# BSB-to-PoELAN.net
KiCad netlist of a schematic drawn in EAGLE
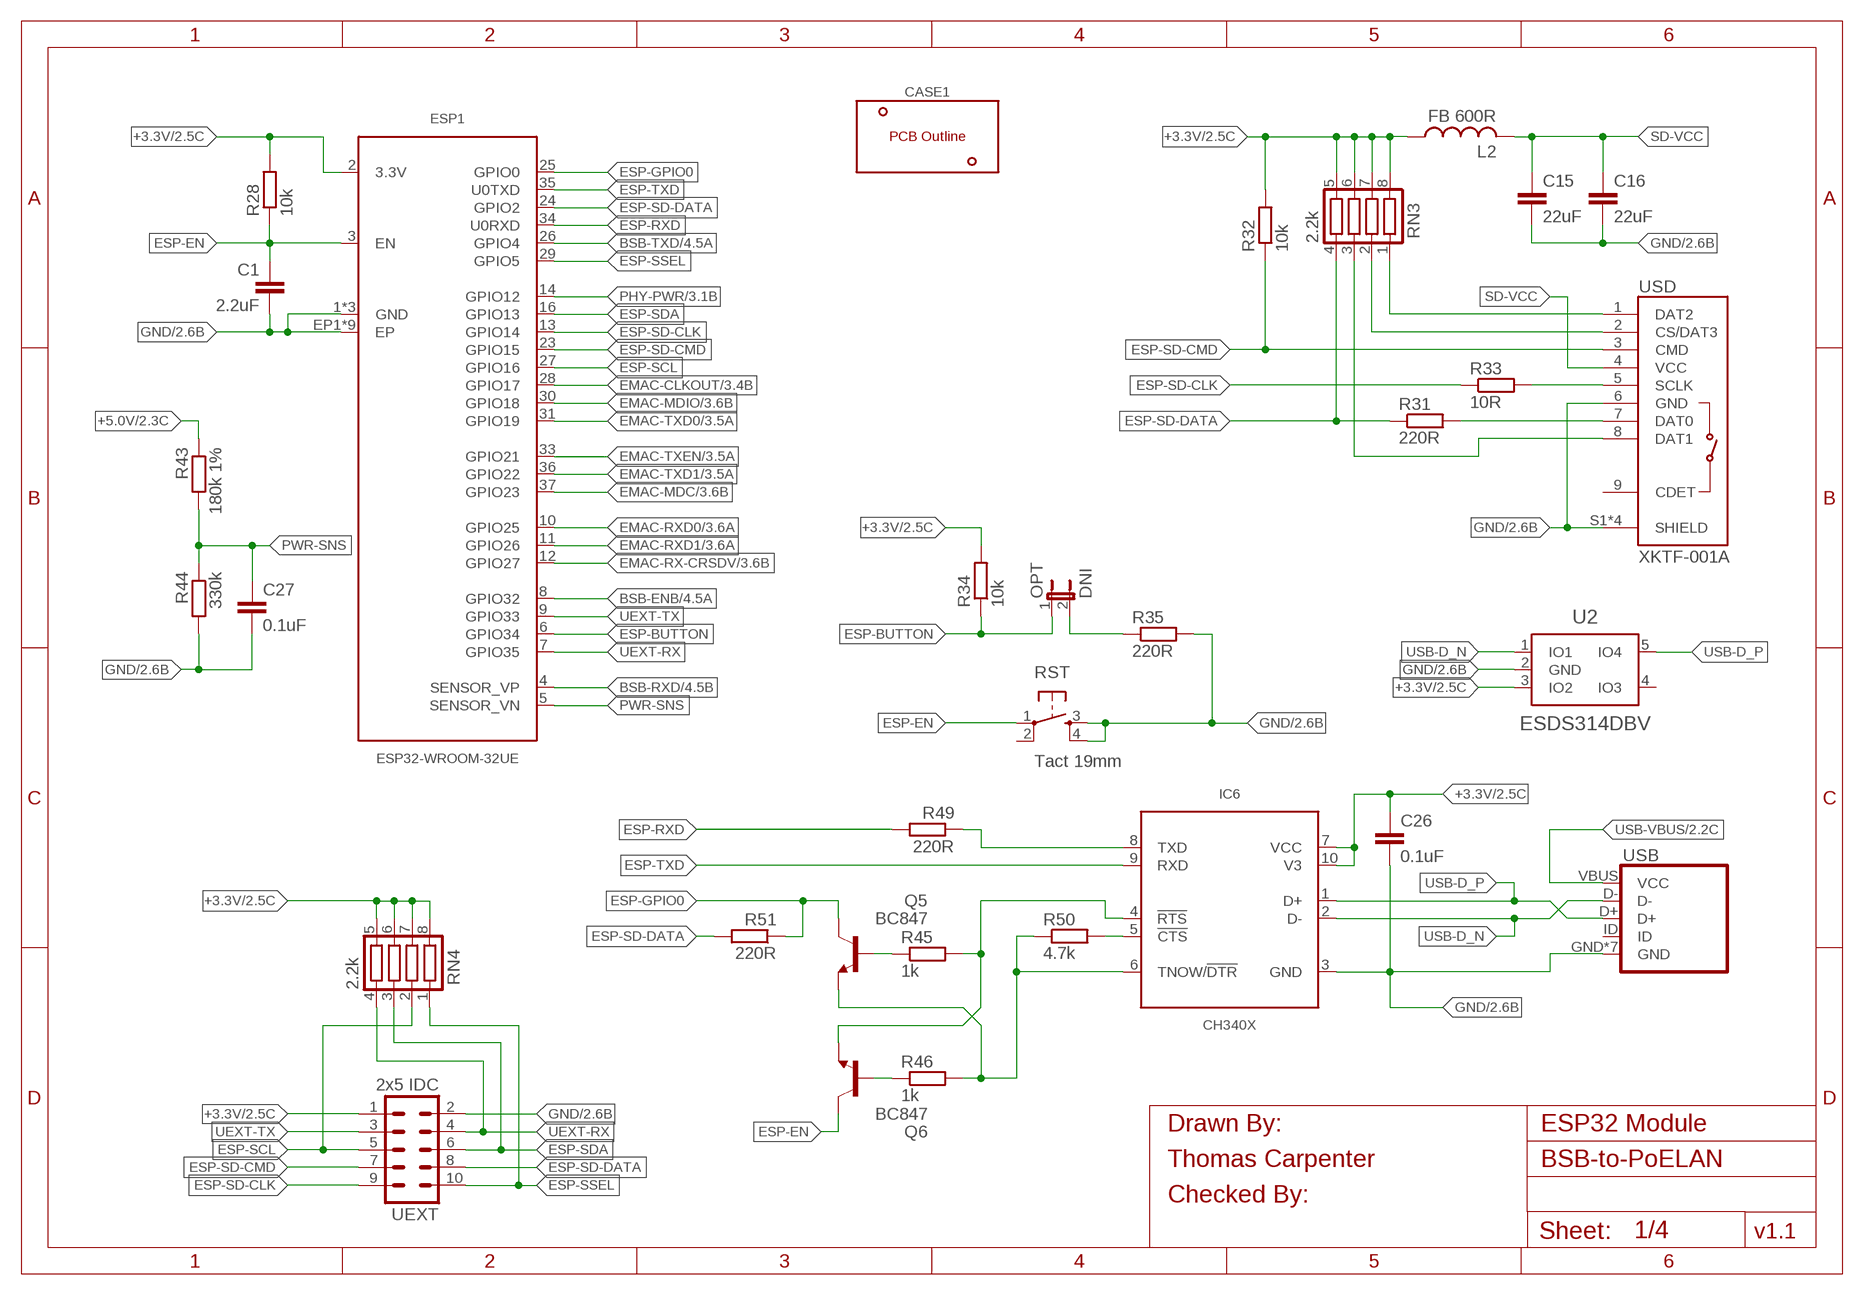
[diagram p0: schematic, sheet 1]
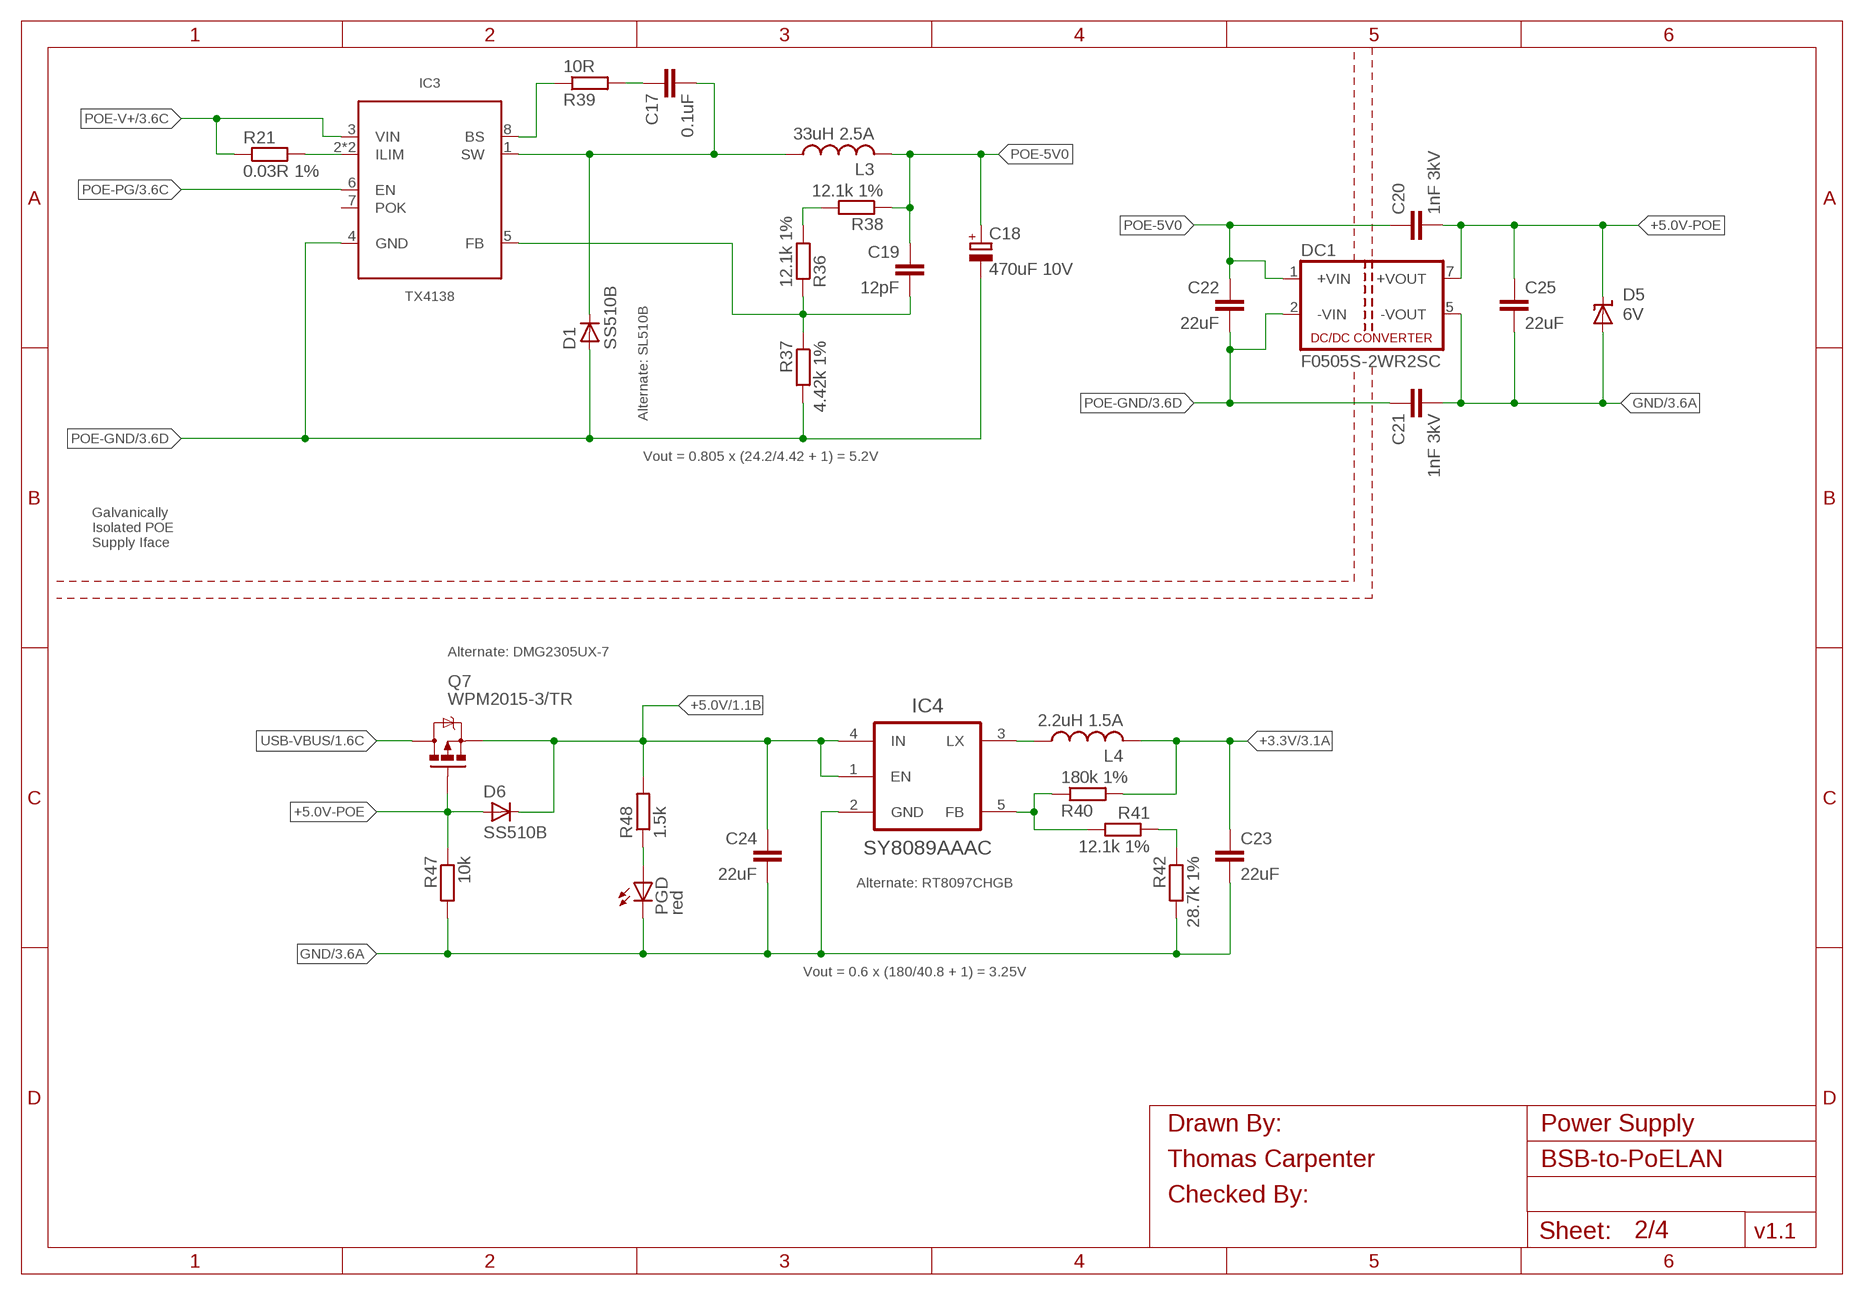
[diagram p1: schematic, sheet 2]
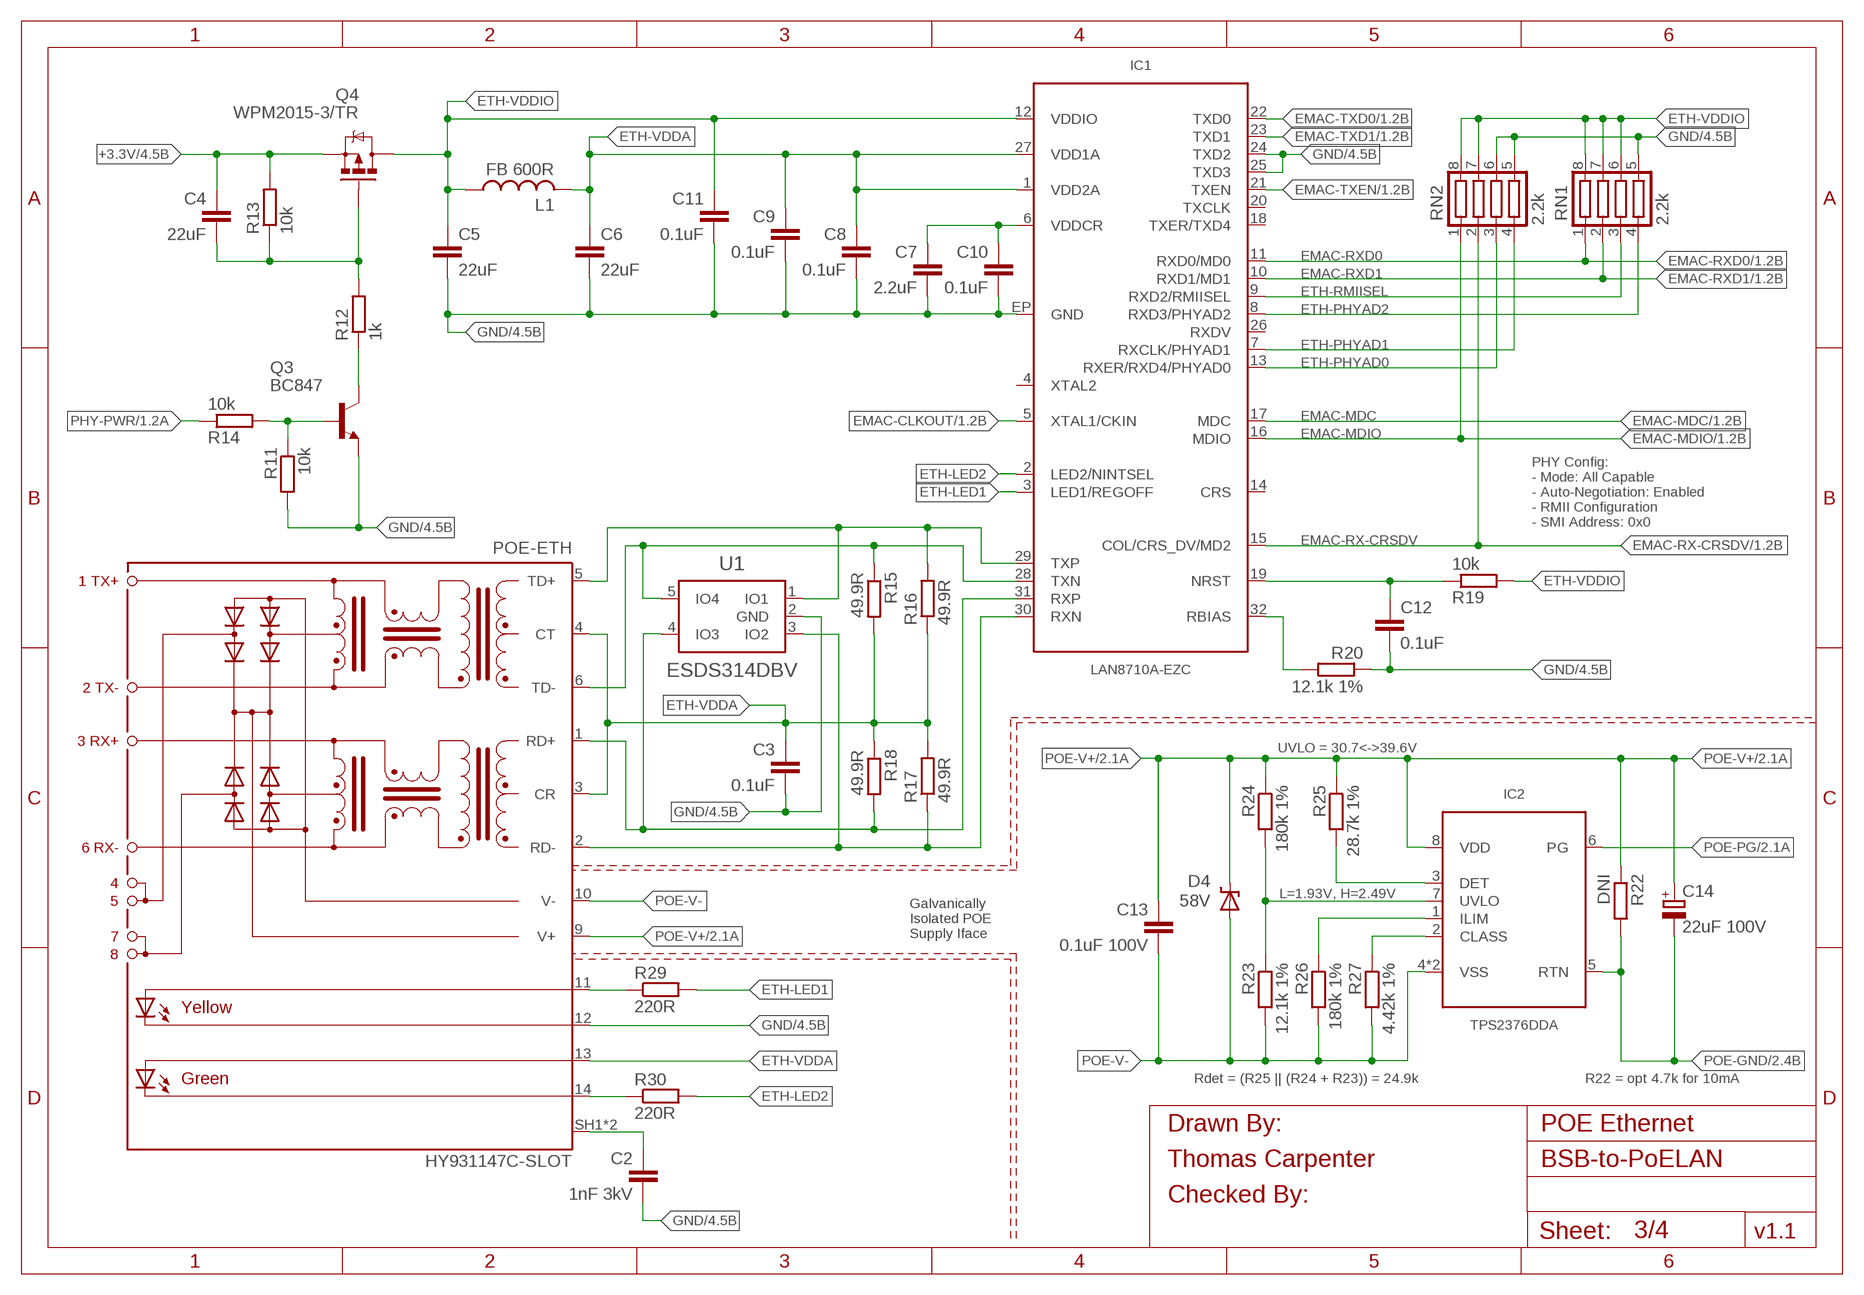
[diagram p2: schematic, sheet 3]
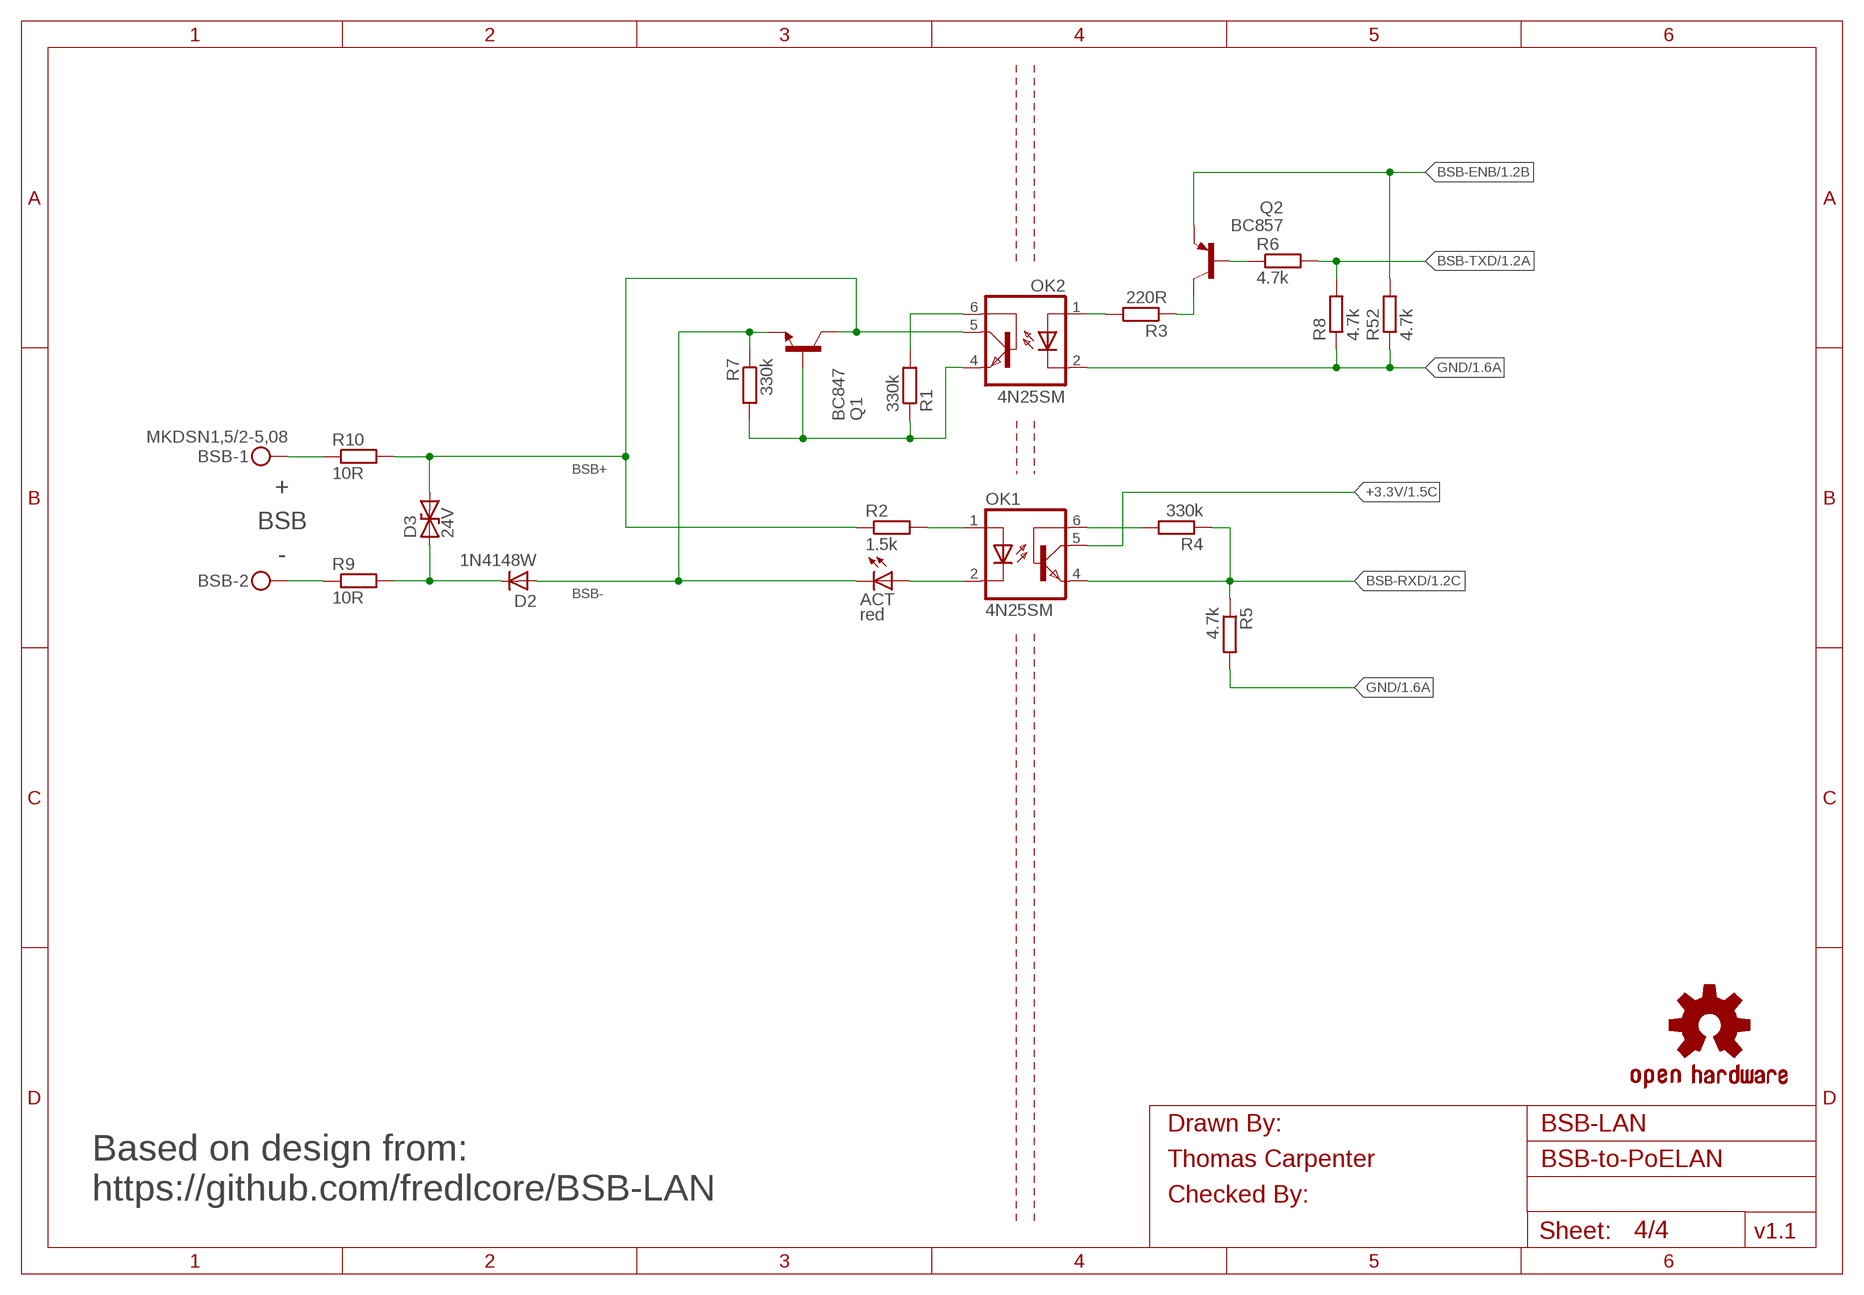
[diagram p3: schematic, sheet 4]

(export (version "E")
  (design (tool "Eeschema 10.0.6"))
  (components
    (comp (ref "C17")
      (value "0.1uF")
      (footprint "eagle-import:C0603L")
      (fields (field (name "LCSC_PART") "C113803"))
      (libsource (lib "eagle-import") (part "C-EUC0603L"))
    )
    (comp (ref "C18")
      (value "470uF 10V")
      (footprint "eagle-import:SMC_D")
      (fields (field (name "LCSC_PART") "C4944894"))
      (libsource (lib "eagle-import") (part "CPOL-EUSMCD"))
    )
    (comp (ref "C19")
      (value "12pF")
      (footprint "eagle-import:C0402")
      (fields (field (name "LCSC_PART") "C1547"))
      (libsource (lib "eagle-import") (part "C-EUC0402"))
    )
    (comp (ref "C20")
      (value "1nF 3kV")
      (footprint "eagle-import:C1808")
      (fields (field (name "LCSC_PART") "C577300"))
      (libsource (lib "eagle-import") (part "C-EUC1808"))
    )
    (comp (ref "C21")
      (value "1nF 3kV")
      (footprint "eagle-import:C1808")
      (fields (field (name "LCSC_PART") "C577300"))
      (libsource (lib "eagle-import") (part "C-EUC1808"))
    )
    (comp (ref "C22")
      (value "22uF")
      (footprint "eagle-import:C0805")
      (fields (field (name "LCSC_PART") "C45783"))
      (libsource (lib "eagle-import") (part "C-EUC0805"))
    )
    (comp (ref "C23")
      (value "22uF")
      (footprint "eagle-import:C0805")
      (fields (field (name "LCSC_PART") "C45783"))
      (libsource (lib "eagle-import") (part "C-EUC0805"))
    )
    (comp (ref "C24")
      (value "22uF")
      (footprint "eagle-import:C0805")
      (fields (field (name "LCSC_PART") "C45783"))
      (libsource (lib "eagle-import") (part "C-EUC0805"))
    )
    (comp (ref "C25")
      (value "22uF")
      (footprint "eagle-import:C0805")
      (fields (field (name "LCSC_PART") "C45783"))
      (libsource (lib "eagle-import") (part "C-EUC0805"))
    )
    (comp (ref "D1")
      (value "SS510B")
      (footprint "eagle-import:SMB")
      (fields (field (name "LCSC_PART") "C65011"))
      (libsource (lib "eagle-import") (part "DIODE-SMB"))
    )
    (comp (ref "D5")
      (value "6V")
      (footprint "eagle-import:SMA")
      (fields (field (name "LCSC_PART") "C223993"))
      (libsource (lib "eagle-import") (part "TVS-UNISMA"))
    )
    (comp (ref "D6")
      (value "SS510B")
      (footprint "eagle-import:SMB")
      (fields (field (name "LCSC_PART") "C65011"))
      (libsource (lib "eagle-import") (part "DIODE-SMB"))
    )
    (comp (ref "DC1")
      (value "F0505S-2WR2SC")
      (footprint "eagle-import:SIP7-N")
      (fields (field (name "LCSC_PART") "C909777"))
      (libsource (lib "eagle-import") (part "FS-2WR2SC0505"))
    )
    (comp (ref "IC3")
      (value "TX4138")
      (footprint "eagle-import:SOIC8-EP")
      (fields (field (name "LCSC_PART") "C329267"))
      (libsource (lib "eagle-import") (part "TX4138"))
    )
    (comp (ref "IC4")
      (value "SY8089AAAC")
      (footprint "eagle-import:DBV0005A-SOT23")
      (fields (field (name "LCSC_PART") "C78988"))
      (libsource (lib "eagle-import") (part "SY8089?CAAA"))
    )
    (comp (ref "L3")
      (value "33uH 2.5A")
      (footprint "eagle-import:L6560P")
      (fields (field (name "LCSC_PART") "C2839927"))
      (libsource (lib "eagle-import") (part "L-USL6560P"))
    )
    (comp (ref "L4")
      (value "2.2uH 1.5A")
      (footprint "eagle-import:L4040P")
      (fields (field (name "LCSC_PART") "C135262"))
      (libsource (lib "eagle-import") (part "L-USL4040P"))
    )
    (comp (ref "PGD")
      (value "red")
      (footprint "eagle-import:CHIP-LED0603")
      (fields (field (name "LCSC_PART") "C2286"))
      (libsource (lib "eagle-import") (part "LEDCHIPLED_0603"))
    )
    (comp (ref "Q7")
      (value "WPM2015-3/TR")
      (footprint "eagle-import:SOT23")
      (fields (field (name "LCSC_PART") "C7472861"))
      (libsource (lib "eagle-import") (part "WPM2015-3/TR"))
    )
    (comp (ref "R21")
      (value "0.03R 1%")
      (footprint "eagle-import:R1206")
      (fields (field (name "LCSC_PART") "C163046"))
      (libsource (lib "eagle-import") (part "R-EU_R1206"))
    )
    (comp (ref "R36")
      (value "12.1k 1%")
      (footprint "eagle-import:R0402")
      (fields (field (name "LCSC_PART") "C25852"))
      (libsource (lib "eagle-import") (part "R-EU_R0402"))
    )
    (comp (ref "R37")
      (value "4.42k 1%")
      (footprint "eagle-import:R0402")
      (fields (field (name "LCSC_PART") "C52269"))
      (libsource (lib "eagle-import") (part "R-EU_R0402"))
    )
    (comp (ref "R38")
      (value "12.1k 1%")
      (footprint "eagle-import:R0402")
      (fields (field (name "LCSC_PART") "C25852"))
      (libsource (lib "eagle-import") (part "R-EU_R0402"))
    )
    (comp (ref "R39")
      (value "10R")
      (footprint "eagle-import:R0603L")
      (fields (field (name "LCSC_PART") "C22859"))
      (libsource (lib "eagle-import") (part "R-EU_R0603L"))
    )
    (comp (ref "R40")
      (value "180k 1%")
      (footprint "eagle-import:R0402")
      (fields (field (name "LCSC_PART") "C25760"))
      (libsource (lib "eagle-import") (part "R-EU_R0402"))
    )
    (comp (ref "R41")
      (value "12.1k 1%")
      (footprint "eagle-import:R0402")
      (fields (field (name "LCSC_PART") "C25852"))
      (libsource (lib "eagle-import") (part "R-EU_R0402"))
    )
    (comp (ref "R42")
      (value "28.7k 1%")
      (footprint "eagle-import:R0402")
      (fields (field (name "LCSC_PART") "C26972"))
      (libsource (lib "eagle-import") (part "R-EU_R0402"))
    )
    (comp (ref "R47")
      (value "10k")
      (footprint "eagle-import:R0402")
      (fields (field (name "LCSC_PART") "C25744"))
      (libsource (lib "eagle-import") (part "R-EU_R0402"))
    )
    (comp (ref "R48")
      (value "1.5k")
      (footprint "eagle-import:R0603")
      (fields (field (name "LCSC_PART") "C22843"))
      (libsource (lib "eagle-import") (part "R-EU_R0603"))
    )
    (comp (ref "C2")
      (value "1nF 3kV")
      (footprint "eagle-import:C1808")
      (fields (field (name "LCSC_PART") "C577300"))
      (libsource (lib "eagle-import") (part "C-EUC1808"))
    )
    (comp (ref "C3")
      (value "0.1uF")
      (footprint "eagle-import:C0402")
      (fields (field (name "LCSC_PART") "C1525"))
      (libsource (lib "eagle-import") (part "C-EUC0402"))
    )
    (comp (ref "C4")
      (value "22uF")
      (footprint "eagle-import:C0805L")
      (fields (field (name "LCSC_PART") "C45783"))
      (libsource (lib "eagle-import") (part "C-EUC0805L"))
    )
    (comp (ref "C5")
      (value "22uF")
      (footprint "eagle-import:C0805L")
      (fields (field (name "LCSC_PART") "C45783"))
      (libsource (lib "eagle-import") (part "C-EUC0805L"))
    )
    (comp (ref "C6")
      (value "22uF")
      (footprint "eagle-import:C0805L")
      (fields (field (name "LCSC_PART") "C45783"))
      (libsource (lib "eagle-import") (part "C-EUC0805L"))
    )
    (comp (ref "C7")
      (value "2.2uF")
      (footprint "eagle-import:C0603")
      (fields (field (name "LCSC_PART") "C23630"))
      (libsource (lib "eagle-import") (part "C-EUC0603"))
    )
    (comp (ref "C8")
      (value "0.1uF")
      (footprint "eagle-import:C0402")
      (fields (field (name "LCSC_PART") "C1525"))
      (libsource (lib "eagle-import") (part "C-EUC0402"))
    )
    (comp (ref "C9")
      (value "0.1uF")
      (footprint "eagle-import:C0402")
      (fields (field (name "LCSC_PART") "C1525"))
      (libsource (lib "eagle-import") (part "C-EUC0402"))
    )
    (comp (ref "C10")
      (value "0.1uF")
      (footprint "eagle-import:C0402")
      (fields (field (name "LCSC_PART") "C1525"))
      (libsource (lib "eagle-import") (part "C-EUC0402"))
    )
    (comp (ref "C11")
      (value "0.1uF")
      (footprint "eagle-import:C0402")
      (fields (field (name "LCSC_PART") "C1525"))
      (libsource (lib "eagle-import") (part "C-EUC0402"))
    )
    (comp (ref "C12")
      (value "0.1uF")
      (footprint "eagle-import:C0402")
      (fields (field (name "LCSC_PART") "C1525"))
      (libsource (lib "eagle-import") (part "C-EUC0402"))
    )
    (comp (ref "C13")
      (value "0.1uF 100V")
      (footprint "eagle-import:C0603")
      (fields (field (name "LCSC_PART") "C113803"))
      (libsource (lib "eagle-import") (part "C-EUC0603"))
    )
    (comp (ref "C14")
      (value "22uF 100V")
      (footprint "eagle-import:PANASONIC_D")
      (fields (field (name "LCSC_PART") "C487431"))
      (libsource (lib "eagle-import") (part "CPOL-EUD"))
    )
    (comp (ref "D4")
      (value "58V")
      (footprint "eagle-import:SMA")
      (fields (field (name "LCSC_PART") "C151246"))
      (libsource (lib "eagle-import") (part "TVS-UNISMA"))
    )
    (comp (ref "IC1")
      (value "LAN8710A-EZC")
      (footprint "eagle-import:QFN-5X5-32")
      (fields (field (name "LCSC_PART") "C46185"))
      (libsource (lib "eagle-import") (part "LAN8710A-EZC"))
    )
    (comp (ref "IC2")
      (value "TPS2376DDA")
      (footprint "eagle-import:SOIC8-EP")
      (fields (field (name "LCSC_PART") "C544899"))
      (libsource (lib "eagle-import") (part "TPS237DDA6"))
    )
    (comp (ref "L1")
      (value "FB 600R")
      (footprint "eagle-import:L2010")
      (fields (field (name "LCSC_PART") "C1017"))
      (libsource (lib "eagle-import") (part "L-USL0805"))
    )
    (comp (ref "POE-ETH")
      (value "HY931147C-SLOT")
      (footprint "eagle-import:HY931147C-SLOT")
      (fields (field (name "LCSC_PART") "C91754"))
      (libsource (lib "eagle-import") (part "HY931147C-SLOT"))
    )
    (comp (ref "Q3")
      (value "BC847")
      (footprint "eagle-import:SOT23")
      (fields (field (name "LCSC_PART") "C130417"))
      (libsource (lib "eagle-import") (part "BC847"))
    )
    (comp (ref "Q4")
      (value "WPM2015-3/TR")
      (footprint "eagle-import:SOT23")
      (fields (field (name "LCSC_PART") "C7472861"))
      (libsource (lib "eagle-import") (part "WPM2015-3/TR"))
    )
    (comp (ref "R11")
      (value "10k")
      (footprint "eagle-import:R0402")
      (fields (field (name "LCSC_PART") "C25744"))
      (libsource (lib "eagle-import") (part "R-EU_R0402"))
    )
    (comp (ref "R12")
      (value "1k")
      (footprint "eagle-import:R0402")
      (fields (field (name "LCSC_PART") "C11702"))
      (libsource (lib "eagle-import") (part "R-EU_R0402"))
    )
    (comp (ref "R13")
      (value "10k")
      (footprint "eagle-import:R0402")
      (fields (field (name "LCSC_PART") "C25744"))
      (libsource (lib "eagle-import") (part "R-EU_R0402"))
    )
    (comp (ref "R14")
      (value "10k")
      (footprint "eagle-import:R0402")
      (fields (field (name "LCSC_PART") "C25744"))
      (libsource (lib "eagle-import") (part "R-EU_R0402"))
    )
    (comp (ref "R15")
      (value "49.9R")
      (footprint "eagle-import:R0402L")
      (fields (field (name "LCSC_PART") "C25120"))
      (libsource (lib "eagle-import") (part "R-EU_R0402L"))
    )
    (comp (ref "R16")
      (value "49.9R")
      (footprint "eagle-import:R0402L")
      (fields (field (name "LCSC_PART") "C25120"))
      (libsource (lib "eagle-import") (part "R-EU_R0402L"))
    )
    (comp (ref "R17")
      (value "49.9R")
      (footprint "eagle-import:R0402L")
      (fields (field (name "LCSC_PART") "C25120"))
      (libsource (lib "eagle-import") (part "R-EU_R0402L"))
    )
    (comp (ref "R18")
      (value "49.9R")
      (footprint "eagle-import:R0402L")
      (fields (field (name "LCSC_PART") "C25120"))
      (libsource (lib "eagle-import") (part "R-EU_R0402L"))
    )
    (comp (ref "R19")
      (value "10k")
      (footprint "eagle-import:R0402")
      (fields (field (name "LCSC_PART") "C25744"))
      (libsource (lib "eagle-import") (part "R-EU_R0402"))
    )
    (comp (ref "R20")
      (value "12.1k 1%")
      (footprint "eagle-import:R0402")
      (fields (field (name "LCSC_PART") "C25852"))
      (libsource (lib "eagle-import") (part "R-EU_R0402"))
    )
    (comp (ref "R22")
      (value "DNI")
      (footprint "eagle-import:R1206")
      (libsource (lib "eagle-import") (part "R-EU_R1206"))
    )
    (comp (ref "R23")
      (value "12.1k 1%")
      (footprint "eagle-import:R0402")
      (fields (field (name "LCSC_PART") "C25852"))
      (libsource (lib "eagle-import") (part "R-EU_R0402"))
    )
    (comp (ref "R24")
      (value "180k 1%")
      (footprint "eagle-import:R0402")
      (fields (field (name "LCSC_PART") "C25760"))
      (libsource (lib "eagle-import") (part "R-EU_R0402"))
    )
    (comp (ref "R25")
      (value "28.7k 1%")
      (footprint "eagle-import:R0402")
      (fields (field (name "LCSC_PART") "C26972"))
      (libsource (lib "eagle-import") (part "R-EU_R0402"))
    )
    (comp (ref "R26")
      (value "180k 1%")
      (footprint "eagle-import:R0402")
      (fields (field (name "LCSC_PART") "C25760"))
      (libsource (lib "eagle-import") (part "R-EU_R0402"))
    )
    (comp (ref "R27")
      (value "4.42k 1%")
      (footprint "eagle-import:R0402")
      (fields (field (name "LCSC_PART") "C52269"))
      (libsource (lib "eagle-import") (part "R-EU_R0402"))
    )
    (comp (ref "R29")
      (value "220R")
      (footprint "eagle-import:R0402")
      (fields (field (name "LCSC_PART") "C25091"))
      (libsource (lib "eagle-import") (part "R-EU_R0402"))
    )
    (comp (ref "R30")
      (value "220R")
      (footprint "eagle-import:R0402")
      (fields (field (name "LCSC_PART") "C25091"))
      (libsource (lib "eagle-import") (part "R-EU_R0402"))
    )
    (comp (ref "RN1")
      (value "2.2k")
      (footprint "eagle-import:CTS742C083")
      (fields (field (name "LCSC_PART") "C414564"))
      (libsource (lib "eagle-import") (part "R-NET-04-R1206"))
    )
    (comp (ref "RN2")
      (value "2.2k")
      (footprint "eagle-import:CTS742C083")
      (fields (field (name "LCSC_PART") "C414564"))
      (libsource (lib "eagle-import") (part "R-NET-04-R1206"))
    )
    (comp (ref "U1")
      (value "ESDS314DBV")
      (footprint "eagle-import:DBV0005A-SOT23")
      (fields (field (name "LCSC_PART") "C1847859"))
      (libsource (lib "eagle-import") (part "ESDS314DBV"))
    )
    (comp (ref "C1")
      (value "2.2uF")
      (footprint "eagle-import:C0603")
      (fields (field (name "LCSC_PART") "C23630"))
      (libsource (lib "eagle-import") (part "C-EUC0603"))
    )
    (comp (ref "C15")
      (value "22uF")
      (footprint "eagle-import:C0805L")
      (fields (field (name "LCSC_PART") "C45783"))
      (libsource (lib "eagle-import") (part "C-EUC0805L"))
    )
    (comp (ref "C16")
      (value "22uF")
      (footprint "eagle-import:C0805L")
      (fields (field (name "LCSC_PART") "C45783"))
      (libsource (lib "eagle-import") (part "C-EUC0805L"))
    )
    (comp (ref "C26")
      (value "0.1uF")
      (footprint "eagle-import:C0402")
      (fields (field (name "LCSC_PART") "C1525"))
      (libsource (lib "eagle-import") (part "C-EUC0402"))
    )
    (comp (ref "C27")
      (value "0.1uF")
      (footprint "eagle-import:C0402")
      (fields (field (name "LCSC_PART") "C1525"))
      (libsource (lib "eagle-import") (part "C-EUC0402"))
    )
    (comp (ref "CASE1")
      (value "DNI")
      (footprint "eagle-import:CNMB_3-")
      (libsource (lib "eagle-import") (part "CNMB/3"))
    )
    (comp (ref "ESP1")
      (value "ESP32-WROOM-32UE")
      (footprint "eagle-import:ESP32-WROOM-32UE")
      (fields (field (name "LCSC_PART") "C701344"))
      (libsource (lib "eagle-import") (part "ESP32-WROOM-32UE"))
    )
    (comp (ref "IC6")
      (value "CH340X")
      (footprint "eagle-import:MSOP10")
      (fields (field (name "LCSC_PART") "C3035748"))
      (libsource (lib "eagle-import") (part "CH340X"))
    )
    (comp (ref "L2")
      (value "FB 600R")
      (footprint "eagle-import:L2010")
      (fields (field (name "LCSC_PART") "C1017"))
      (libsource (lib "eagle-import") (part "L-USL0805"))
    )
    (comp (ref "OPT")
      (value "DNI")
      (footprint "eagle-import:1X02")
      (libsource (lib "eagle-import") (part "JUMPER-2-PTH"))
    )
    (comp (ref "Q5")
      (value "BC847")
      (footprint "eagle-import:SOT23")
      (fields (field (name "LCSC_PART") "C130417") (field (name "LCSC_PART_1") "C130417"))
      (libsource (lib "eagle-import") (part "BC847"))
    )
    (comp (ref "Q6")
      (value "BC847")
      (footprint "eagle-import:SOT23")
      (fields (field (name "LCSC_PART") "C130417"))
      (libsource (lib "eagle-import") (part "BC847"))
    )
    (comp (ref "R28")
      (value "10k")
      (footprint "eagle-import:R0402")
      (fields (field (name "LCSC_PART") "C25744"))
      (libsource (lib "eagle-import") (part "R-EU_R0402"))
    )
    (comp (ref "R31")
      (value "220R")
      (footprint "eagle-import:R0402")
      (fields (field (name "LCSC_PART") "C25091"))
      (libsource (lib "eagle-import") (part "R-EU_R0402"))
    )
    (comp (ref "R32")
      (value "10k")
      (footprint "eagle-import:R0402")
      (fields (field (name "LCSC_PART") "C25744"))
      (libsource (lib "eagle-import") (part "R-EU_R0402"))
    )
    (comp (ref "R33")
      (value "10R")
      (footprint "eagle-import:R0603L")
      (fields (field (name "LCSC_PART") "C22859"))
      (libsource (lib "eagle-import") (part "R-EU_R0603L"))
    )
    (comp (ref "R34")
      (value "10k")
      (footprint "eagle-import:R0402")
      (fields (field (name "LCSC_PART") "C25744"))
      (libsource (lib "eagle-import") (part "R-EU_R0402"))
    )
    (comp (ref "R35")
      (value "220R")
      (footprint "eagle-import:R0402")
      (fields (field (name "LCSC_PART") "C25091"))
      (libsource (lib "eagle-import") (part "R-EU_R0402"))
    )
    (comp (ref "R43")
      (value "180k 1%")
      (footprint "eagle-import:R0402")
      (fields (field (name "LCSC_PART") "C25760"))
      (libsource (lib "eagle-import") (part "R-EU_R0402"))
    )
    (comp (ref "R44")
      (value "330k")
      (footprint "eagle-import:R0603L")
      (fields (field (name "LCSC_PART") "C23137"))
      (libsource (lib "eagle-import") (part "R-EU_R0603L"))
    )
    (comp (ref "R45")
      (value "1k")
      (footprint "eagle-import:R0402")
      (fields (field (name "LCSC_PART") "C11702"))
      (libsource (lib "eagle-import") (part "R-EU_R0402"))
    )
    (comp (ref "R46")
      (value "1k")
      (footprint "eagle-import:R0402")
      (fields (field (name "LCSC_PART") "C11702"))
      (libsource (lib "eagle-import") (part "R-EU_R0402"))
    )
    (comp (ref "R49")
      (value "220R")
      (footprint "eagle-import:R0402")
      (fields (field (name "LCSC_PART") "C25091"))
      (libsource (lib "eagle-import") (part "R-EU_R0402"))
    )
    (comp (ref "R50")
      (value "4.7k")
      (footprint "eagle-import:R0402")
      (fields (field (name "LCSC_PART") "C25900"))
      (libsource (lib "eagle-import") (part "R-EU_R0402"))
    )
    (comp (ref "R51")
      (value "220R")
      (footprint "eagle-import:R0402")
      (fields (field (name "LCSC_PART") "C25091"))
      (libsource (lib "eagle-import") (part "R-EU_R0402"))
    )
    (comp (ref "RN3")
      (value "2.2k")
      (footprint "eagle-import:CTS742C083")
      (fields (field (name "LCSC_PART") "C414564"))
      (libsource (lib "eagle-import") (part "R-NET-04-R1206"))
    )
    (comp (ref "RN4")
      (value "2.2k")
      (footprint "eagle-import:CTS742C083")
      (fields (field (name "LCSC_PART") "C414564"))
      (libsource (lib "eagle-import") (part "R-NET-04-R1206"))
    )
    (comp (ref "RST")
      (value "Tact 19mm")
      (footprint "eagle-import:TACTILE_SWITCH")
      (fields (field (name "LCSC_PART") "C13828") (field (name "LCSC_PART_1") "C2837529"))
      (libsource (lib "eagle-import") (part "SWITCH-MOMENTARY"))
    )
    (comp (ref "U2")
      (value "ESDS314DBV")
      (footprint "eagle-import:DBV0005A-SOT23")
      (fields (field (name "LCSC_PART") "C1847859"))
      (libsource (lib "eagle-import") (part "ESDS314DBV"))
    )
    (comp (ref "UEXT")
      (value "2x5 IDC")
      (footprint "eagle-import:ML10")
      (fields (field (name "LCSC_PART") "C5665"))
      (libsource (lib "eagle-import") (part "ML10"))
    )
    (comp (ref "USB")
      (value "ZX62-B-5PA(33)")
      (footprint "eagle-import:USB-MICROB")
      (fields (field (name "LCSC_PART") "C132561"))
      (libsource (lib "eagle-import") (part "USB_MICROB_PLUG"))
    )
    (comp (ref "USD")
      (value "XKTF-001A")
      (footprint "eagle-import:MICRO-SD")
      (fields (field (name "LCSC_PART") "C381079"))
      (libsource (lib "eagle-import") (part "MICROSD"))
    )
    (comp (ref "ACT")
      (value "red")
      (footprint "eagle-import:CHIP-LED0603")
      (fields (field (name "LCSC_PART") "C2286"))
      (libsource (lib "eagle-import") (part "LEDCHIPLED_0603"))
    )
    (comp (ref "BSB")
      (value "MKDSN1,5/2-5,08")
      (footprint "eagle-import:MKDSN1_5-2-5_08")
      (fields (field (name "LCSC_PART") "C5183989"))
      (libsource (lib "eagle-import") (part "MKDSN1,5/2-5,08"))
    )
    (comp (ref "D2")
      (value "1N4148W")
      (footprint "eagle-import:SOD123")
      (fields (field (name "LCSC_PART") "C81598"))
      (libsource (lib "eagle-import") (part "DIODE-SOD123"))
    )
    (comp (ref "D3")
      (value "24V")
      (footprint "eagle-import:SMBG")
      (fields (field (name "LCSC_PART") "C83268"))
      (libsource (lib "eagle-import") (part "TVS-BIDIRSMB"))
    )
    (comp (ref "OK1")
      (value "4N25SM")
      (footprint "eagle-import:DIL6-SMD")
      (fields (field (name "LCSC_PART") "C258246") (field (name "LCSC_PART_1") "C258246"))
      (libsource (lib "eagle-import") (part "4N?MS25"))
    )
    (comp (ref "OK2")
      (value "4N25SM")
      (footprint "eagle-import:DIL6-SMD")
      (fields (field (name "LCSC_PART") "C258246") (field (name "LCSC_PART_1") "C258246"))
      (libsource (lib "eagle-import") (part "4N?MS25"))
    )
    (comp (ref "Q1")
      (value "BC847")
      (footprint "eagle-import:SOT23")
      (fields (field (name "LCSC_PART") "C130417") (field (name "LCSC_PART_1") "C130417"))
      (libsource (lib "eagle-import") (part "BC847"))
    )
    (comp (ref "Q2")
      (value "BC857")
      (footprint "eagle-import:SOT23-BEC")
      (fields (field (name "LCSC_PART") "C426782") (field (name "LCSC_PART_1") "C426782"))
      (libsource (lib "eagle-import") (part "BC857"))
    )
    (comp (ref "R1")
      (value "330k")
      (footprint "eagle-import:R0603")
      (fields (field (name "LCSC_PART") "C23137"))
      (libsource (lib "eagle-import") (part "R-EU_R0603"))
    )
    (comp (ref "R2")
      (value "1.5k")
      (footprint "eagle-import:R0603")
      (fields (field (name "LCSC_PART") "C22843"))
      (libsource (lib "eagle-import") (part "R-EU_R0603"))
    )
    (comp (ref "R3")
      (value "220R")
      (footprint "eagle-import:R0402")
      (fields (field (name "LCSC_PART") "C25091"))
      (libsource (lib "eagle-import") (part "R-EU_R0402"))
    )
    (comp (ref "R4")
      (value "330k")
      (footprint "eagle-import:R0603")
      (fields (field (name "LCSC_PART") "C23137"))
      (libsource (lib "eagle-import") (part "R-EU_R0603"))
    )
    (comp (ref "R5")
      (value "4.7k")
      (footprint "eagle-import:R0402")
      (fields (field (name "LCSC_PART") "C25900"))
      (libsource (lib "eagle-import") (part "R-EU_R0402"))
    )
    (comp (ref "R6")
      (value "4.7k")
      (footprint "eagle-import:R0402")
      (fields (field (name "LCSC_PART") "C25900"))
      (libsource (lib "eagle-import") (part "R-EU_R0402"))
    )
    (comp (ref "R7")
      (value "330k")
      (footprint "eagle-import:R0603")
      (fields (field (name "LCSC_PART") "C23137"))
      (libsource (lib "eagle-import") (part "R-EU_R0603"))
    )
    (comp (ref "R8")
      (value "4.7k")
      (footprint "eagle-import:R0402")
      (fields (field (name "LCSC_PART") "C25900"))
      (libsource (lib "eagle-import") (part "R-EU_R0402"))
    )
    (comp (ref "R9")
      (value "10R")
      (footprint "eagle-import:R0603")
      (fields (field (name "LCSC_PART") "C22859"))
      (libsource (lib "eagle-import") (part "R-EU_R0603"))
    )
    (comp (ref "R10")
      (value "10R")
      (footprint "eagle-import:R0603")
      (fields (field (name "LCSC_PART") "C22859"))
      (libsource (lib "eagle-import") (part "R-EU_R0603"))
    )
    (comp (ref "R52")
      (value "4.7k")
      (footprint "eagle-import:R0402")
      (fields (field (name "LCSC_PART") "C25900"))
      (libsource (lib "eagle-import") (part "R-EU_R0402"))
    )
    (comp (ref "U$3")
      (value "DNI")
      (footprint "eagle-import:OSHW-LOGO-M")
      (libsource (lib "eagle-import") (part "OSHW-LOGOM"))
    )
  )
  (nets
    (net (code "1") (name "+3.3V") (class "Default")
      (node (ref "C23") (pin "1") (pinfunction "1_1") (pintype "passive"))
      (node (ref "C26") (pin "1") (pinfunction "1_1") (pintype "passive"))
      (node (ref "C4") (pin "1") (pinfunction "1_1") (pintype "passive"))
      (node (ref "ESP1") (pin "2") (pinfunction "3.3V_2") (pintype "power_in"))
      (node (ref "IC6") (pin "10") (pinfunction "V3_10") (pintype "power_in"))
      (node (ref "IC6") (pin "7") (pinfunction "VCC_7") (pintype "power_in"))
      (node (ref "L2") (pin "1") (pinfunction "1_1") (pintype "passive"))
      (node (ref "L4") (pin "2") (pinfunction "2_2") (pintype "passive"))
      (node (ref "OK1") (pin "5") (pinfunction "COL_5") (pintype "passive"))
      (node (ref "Q4") (pin "2") (pinfunction "S_2") (pintype "passive"))
      (node (ref "R13") (pin "2") (pinfunction "2_2") (pintype "passive"))
      (node (ref "R28") (pin "2") (pinfunction "2_2") (pintype "passive"))
      (node (ref "R32") (pin "2") (pinfunction "2_2") (pintype "passive"))
      (node (ref "R34") (pin "2") (pinfunction "2_2") (pintype "passive"))
      (node (ref "R40") (pin "2") (pinfunction "2_2") (pintype "passive"))
      (node (ref "RN3") (pin "5") (pinfunction "5_5") (pintype "passive"))
      (node (ref "RN3") (pin "6") (pinfunction "6_6") (pintype "passive"))
      (node (ref "RN3") (pin "7") (pinfunction "7_7") (pintype "passive"))
      (node (ref "RN3") (pin "8") (pinfunction "8_8") (pintype "passive"))
      (node (ref "RN4") (pin "5") (pinfunction "5_5") (pintype "passive"))
      (node (ref "RN4") (pin "6") (pinfunction "6_6") (pintype "passive"))
      (node (ref "RN4") (pin "7") (pinfunction "7_7") (pintype "passive"))
      (node (ref "RN4") (pin "8") (pinfunction "8_8") (pintype "passive"))
      (node (ref "U2") (pin "3") (pinfunction "IO2_3") (pintype "passive"))
      (node (ref "UEXT") (pin "1") (pinfunction "1_1") (pintype "passive"))
    )
    (net (code "2") (name "+5.0V") (class "Default")
      (node (ref "C24") (pin "1") (pinfunction "1_1") (pintype "passive"))
      (node (ref "D6") (pin "C") (pinfunction "C_C") (pintype "passive"))
      (node (ref "IC4") (pin "1") (pinfunction "EN_1") (pintype "input"))
      (node (ref "IC4") (pin "4") (pinfunction "IN_4") (pintype "power_in"))
      (node (ref "Q7") (pin "2") (pinfunction "S_2") (pintype "passive"))
      (node (ref "R43") (pin "1") (pinfunction "1_1") (pintype "passive"))
      (node (ref "R48") (pin "2") (pinfunction "2_2") (pintype "passive"))
    )
    (net (code "3") (name "+5.0V-POE") (class "Default")
      (node (ref "C20") (pin "2") (pinfunction "2_2") (pintype "passive"))
      (node (ref "C25") (pin "1") (pinfunction "1_1") (pintype "passive"))
      (node (ref "D5") (pin "C") (pinfunction "C_C") (pintype "passive"))
      (node (ref "D6") (pin "A") (pinfunction "A_A") (pintype "passive"))
      (node (ref "DC1") (pin "7") (pinfunction "+VOUT_7") (pintype "passive"))
      (node (ref "Q7") (pin "1") (pinfunction "G_1") (pintype "passive"))
      (node (ref "R47") (pin "1") (pinfunction "1_1") (pintype "passive"))
    )
    (net (code "4") (name "BSB+") (class "Default")
      (node (ref "D3") (pin "2") (pinfunction "2_2") (pintype "passive"))
      (node (ref "OK2") (pin "5") (pinfunction "COL_5") (pintype "passive"))
      (node (ref "Q1") (pin "3") (pinfunction "C_3") (pintype "passive"))
      (node (ref "R10") (pin "2") (pinfunction "2_2") (pintype "passive"))
      (node (ref "R2") (pin "1") (pinfunction "1_1") (pintype "passive"))
    )
    (net (code "5") (name "BSB-") (class "Default")
      (node (ref "ACT") (pin "C") (pinfunction "C_C") (pintype "passive"))
      (node (ref "D2") (pin "A") (pinfunction "A_A") (pintype "passive"))
      (node (ref "Q1") (pin "2") (pinfunction "E_2") (pintype "passive"))
      (node (ref "R7") (pin "1") (pinfunction "1_1") (pintype "passive"))
    )
    (net (code "6") (name "BSB-ENB") (class "Default")
      (node (ref "ESP1") (pin "8") (pinfunction "GPIO32_8") (pintype "bidirectional"))
      (node (ref "Q2") (pin "E") (pinfunction "E_E") (pintype "passive"))
      (node (ref "R52") (pin "2") (pinfunction "2_2") (pintype "passive"))
    )
    (net (code "7") (name "BSB-RXD") (class "Default")
      (node (ref "ESP1") (pin "4") (pinfunction "SENSOR_VP_4") (pintype "bidirectional"))
      (node (ref "OK1") (pin "4") (pinfunction "EMI_4") (pintype "passive"))
      (node (ref "R4") (pin "1") (pinfunction "1_1") (pintype "passive"))
      (node (ref "R5") (pin "1") (pinfunction "1_1") (pintype "passive"))
    )
    (net (code "8") (name "BSB-TXD") (class "Default")
      (node (ref "ESP1") (pin "26") (pinfunction "GPIO4_26") (pintype "bidirectional"))
      (node (ref "R6") (pin "2") (pinfunction "2_2") (pintype "passive"))
      (node (ref "R8") (pin "2") (pinfunction "2_2") (pintype "passive"))
    )
    (net (code "9") (name "EMAC-CLKOUT") (class "Default")
      (node (ref "ESP1") (pin "28") (pinfunction "GPIO17_28") (pintype "bidirectional"))
      (node (ref "IC1") (pin "5") (pinfunction "XTAL1/CKIN_5") (pintype "input"))
    )
    (net (code "10") (name "EMAC-MDC") (class "Default")
      (node (ref "ESP1") (pin "37") (pinfunction "GPIO23_37") (pintype "bidirectional"))
      (node (ref "IC1") (pin "17") (pinfunction "MDC_17") (pintype "input"))
    )
    (net (code "11") (name "EMAC-MDIO") (class "Default")
      (node (ref "ESP1") (pin "30") (pinfunction "GPIO18_30") (pintype "bidirectional"))
      (node (ref "IC1") (pin "16") (pinfunction "MDIO_16") (pintype "bidirectional"))
      (node (ref "RN2") (pin "1") (pinfunction "1_1") (pintype "passive"))
    )
    (net (code "12") (name "EMAC-RX-CRSDV") (class "Default")
      (node (ref "ESP1") (pin "12") (pinfunction "GPIO27_12") (pintype "bidirectional"))
      (node (ref "IC1") (pin "15") (pinfunction "COL/CRS_DV/MD2_15") (pintype "bidirectional"))
      (node (ref "RN2") (pin "2") (pinfunction "2_2") (pintype "passive"))
    )
    (net (code "13") (name "EMAC-RXD0") (class "Default")
      (node (ref "ESP1") (pin "10") (pinfunction "GPIO25_10") (pintype "bidirectional"))
      (node (ref "IC1") (pin "11") (pinfunction "RXD0/MD0_11") (pintype "bidirectional"))
      (node (ref "RN1") (pin "1") (pinfunction "1_1") (pintype "passive"))
    )
    (net (code "14") (name "EMAC-RXD1") (class "Default")
      (node (ref "ESP1") (pin "11") (pinfunction "GPIO26_11") (pintype "bidirectional"))
      (node (ref "IC1") (pin "10") (pinfunction "RXD1/MD1_10") (pintype "bidirectional"))
      (node (ref "RN1") (pin "2") (pinfunction "2_2") (pintype "passive"))
    )
    (net (code "15") (name "EMAC-TXD0") (class "Default")
      (node (ref "ESP1") (pin "31") (pinfunction "GPIO19_31") (pintype "bidirectional"))
      (node (ref "IC1") (pin "22") (pinfunction "TXD0_22") (pintype "input"))
    )
    (net (code "16") (name "EMAC-TXD1") (class "Default")
      (node (ref "ESP1") (pin "36") (pinfunction "GPIO22_36") (pintype "bidirectional"))
      (node (ref "IC1") (pin "23") (pinfunction "TXD1_23") (pintype "input"))
    )
    (net (code "17") (name "EMAC-TXEN") (class "Default")
      (node (ref "ESP1") (pin "33") (pinfunction "GPIO21_33") (pintype "bidirectional"))
      (node (ref "IC1") (pin "21") (pinfunction "TXEN_21") (pintype "input"))
    )
    (net (code "18") (name "ESP-BUTTON") (class "Default")
      (node (ref "ESP1") (pin "6") (pinfunction "GPIO34_6") (pintype "bidirectional"))
      (node (ref "OPT") (pin "1") (pinfunction "1_1") (pintype "passive"))
      (node (ref "R34") (pin "1") (pinfunction "1_1") (pintype "passive"))
    )
    (net (code "19") (name "ESP-EN") (class "Default")
      (node (ref "C1") (pin "1") (pinfunction "1_1") (pintype "passive"))
      (node (ref "ESP1") (pin "3") (pinfunction "EN_3") (pintype "input"))
      (node (ref "Q6") (pin "3") (pinfunction "C_3") (pintype "passive"))
      (node (ref "R28") (pin "1") (pinfunction "1_1") (pintype "passive"))
      (node (ref "RST") (pin "1") (pinfunction "1_1") (pintype "passive"))
    )
    (net (code "20") (name "ESP-GPIO0") (class "Default")
      (node (ref "ESP1") (pin "25") (pinfunction "GPIO0_25") (pintype "bidirectional"))
      (node (ref "Q5") (pin "3") (pinfunction "C_3") (pintype "passive"))
      (node (ref "R51") (pin "1") (pinfunction "1_1") (pintype "passive"))
    )
    (net (code "21") (name "ESP-RXD") (class "Default")
      (node (ref "ESP1") (pin "34") (pinfunction "U0RXD_34") (pintype "bidirectional"))
      (node (ref "R49") (pin "2") (pinfunction "2_2") (pintype "passive"))
    )
    (net (code "22") (name "ESP-SCL") (class "Default")
      (node (ref "ESP1") (pin "27") (pinfunction "GPIO16_27") (pintype "bidirectional"))
      (node (ref "RN4") (pin "2") (pinfunction "2_2") (pintype "passive"))
      (node (ref "UEXT") (pin "5") (pinfunction "5_5") (pintype "passive"))
    )
    (net (code "23") (name "ESP-SD-CLK") (class "Default")
      (node (ref "ESP1") (pin "13") (pinfunction "GPIO14_13") (pintype "bidirectional"))
      (node (ref "R33") (pin "1") (pinfunction "1_1") (pintype "passive"))
      (node (ref "UEXT") (pin "9") (pinfunction "9_9") (pintype "passive"))
    )
    (net (code "24") (name "ESP-SD-CMD") (class "Default")
      (node (ref "ESP1") (pin "23") (pinfunction "GPIO15_23") (pintype "bidirectional"))
      (node (ref "R32") (pin "1") (pinfunction "1_1") (pintype "passive"))
      (node (ref "UEXT") (pin "7") (pinfunction "7_7") (pintype "passive"))
      (node (ref "USD") (pin "3") (pinfunction "CMD_3") (pintype "bidirectional"))
    )
    (net (code "25") (name "ESP-SD-DATA") (class "Default")
      (node (ref "ESP1") (pin "24") (pinfunction "GPIO2_24") (pintype "bidirectional"))
      (node (ref "R31") (pin "1") (pinfunction "1_1") (pintype "passive"))
      (node (ref "R51") (pin "2") (pinfunction "2_2") (pintype "passive"))
      (node (ref "RN3") (pin "4") (pinfunction "4_4") (pintype "passive"))
      (node (ref "UEXT") (pin "8") (pinfunction "8_8") (pintype "passive"))
    )
    (net (code "26") (name "ESP-SDA") (class "Default")
      (node (ref "ESP1") (pin "16") (pinfunction "GPIO13_16") (pintype "bidirectional"))
      (node (ref "RN4") (pin "3") (pinfunction "3_3") (pintype "passive"))
      (node (ref "UEXT") (pin "6") (pinfunction "6_6") (pintype "passive"))
    )
    (net (code "27") (name "ESP-SSEL") (class "Default")
      (node (ref "ESP1") (pin "29") (pinfunction "GPIO5_29") (pintype "bidirectional"))
      (node (ref "RN4") (pin "1") (pinfunction "1_1") (pintype "passive"))
      (node (ref "UEXT") (pin "10") (pinfunction "10_10") (pintype "passive"))
    )
    (net (code "28") (name "ESP-TXD") (class "Default")
      (node (ref "ESP1") (pin "35") (pinfunction "U0TXD_35") (pintype "bidirectional"))
      (node (ref "IC6") (pin "9") (pinfunction "RXD_9") (pintype "input"))
    )
    (net (code "29") (name "ETH-LED1") (class "Default")
      (node (ref "IC1") (pin "3") (pinfunction "LED1/REGOFF_3") (pintype "bidirectional"))
      (node (ref "R29") (pin "2") (pinfunction "2_2") (pintype "passive"))
    )
    (net (code "30") (name "ETH-LED2") (class "Default")
      (node (ref "IC1") (pin "2") (pinfunction "LED2/NINTSEL_2") (pintype "bidirectional"))
      (node (ref "R30") (pin "2") (pinfunction "2_2") (pintype "passive"))
    )
    (net (code "31") (name "ETH-PHYAD0") (class "Default")
      (node (ref "IC1") (pin "13") (pinfunction "RXER/RXD4/PHYAD0_13") (pintype "bidirectional"))
      (node (ref "RN2") (pin "3") (pinfunction "3_3") (pintype "passive"))
    )
    (net (code "32") (name "ETH-PHYAD1") (class "Default")
      (node (ref "IC1") (pin "7") (pinfunction "RXCLK/PHYAD1_7") (pintype "bidirectional"))
      (node (ref "RN2") (pin "4") (pinfunction "4_4") (pintype "passive"))
    )
    (net (code "33") (name "ETH-PHYAD2") (class "Default")
      (node (ref "IC1") (pin "8") (pinfunction "RXD3/PHYAD2_8") (pintype "bidirectional"))
      (node (ref "RN1") (pin "4") (pinfunction "4_4") (pintype "passive"))
    )
    (net (code "34") (name "ETH-RMIISEL") (class "Default")
      (node (ref "IC1") (pin "9") (pinfunction "RXD2/RMIISEL_9") (pintype "bidirectional"))
      (node (ref "RN1") (pin "3") (pinfunction "3_3") (pintype "passive"))
    )
    (net (code "35") (name "ETH-VDDA") (class "Default")
      (node (ref "C3") (pin "1") (pinfunction "1_1") (pintype "passive"))
      (node (ref "C6") (pin "1") (pinfunction "1_1") (pintype "passive"))
      (node (ref "C8") (pin "1") (pinfunction "1_1") (pintype "passive"))
      (node (ref "C9") (pin "1") (pinfunction "1_1") (pintype "passive"))
      (node (ref "IC1") (pin "1") (pinfunction "VDD2A_1") (pintype "power_in"))
      (node (ref "IC1") (pin "27") (pinfunction "VDD1A_27") (pintype "power_in"))
      (node (ref "L1") (pin "2") (pinfunction "2_2") (pintype "passive"))
      (node (ref "POE-ETH") (pin "13") (pinfunction "GA_13") (pintype "passive"))
      (node (ref "POE-ETH") (pin "3") (pinfunction "CR_3") (pintype "passive"))
      (node (ref "POE-ETH") (pin "4") (pinfunction "CT_4") (pintype "passive"))
      (node (ref "R15") (pin "2") (pinfunction "2_2") (pintype "passive"))
      (node (ref "R16") (pin "1") (pinfunction "1_1") (pintype "passive"))
      (node (ref "R17") (pin "2") (pinfunction "2_2") (pintype "passive"))
      (node (ref "R18") (pin "1") (pinfunction "1_1") (pintype "passive"))
    )
    (net (code "36") (name "ETH-VDDIO") (class "Default")
      (node (ref "C11") (pin "1") (pinfunction "1_1") (pintype "passive"))
      (node (ref "C5") (pin "1") (pinfunction "1_1") (pintype "passive"))
      (node (ref "IC1") (pin "12") (pinfunction "VDDIO_12") (pintype "power_in"))
      (node (ref "L1") (pin "1") (pinfunction "1_1") (pintype "passive"))
      (node (ref "Q4") (pin "3") (pinfunction "D_3") (pintype "passive"))
      (node (ref "R19") (pin "2") (pinfunction "2_2") (pintype "passive"))
      (node (ref "RN1") (pin "6") (pinfunction "6_6") (pintype "passive"))
      (node (ref "RN1") (pin "7") (pinfunction "7_7") (pintype "passive"))
      (node (ref "RN1") (pin "8") (pinfunction "8_8") (pintype "passive"))
      (node (ref "RN2") (pin "7") (pinfunction "7_7") (pintype "passive"))
      (node (ref "RN2") (pin "8") (pinfunction "8_8") (pintype "passive"))
    )
    (net (code "37") (name "GND") (class "Default")
      (node (ref "C1") (pin "2") (pinfunction "2_2") (pintype "passive"))
      (node (ref "C10") (pin "2") (pinfunction "2_2") (pintype "passive"))
      (node (ref "C11") (pin "2") (pinfunction "2_2") (pintype "passive"))
      (node (ref "C12") (pin "2") (pinfunction "2_2") (pintype "passive"))
      (node (ref "C15") (pin "2") (pinfunction "2_2") (pintype "passive"))
      (node (ref "C16") (pin "2") (pinfunction "2_2") (pintype "passive"))
      (node (ref "C2") (pin "2") (pinfunction "2_2") (pintype "passive"))
      (node (ref "C21") (pin "2") (pinfunction "2_2") (pintype "passive"))
      (node (ref "C23") (pin "2") (pinfunction "2_2") (pintype "passive"))
      (node (ref "C24") (pin "2") (pinfunction "2_2") (pintype "passive"))
      (node (ref "C25") (pin "2") (pinfunction "2_2") (pintype "passive"))
      (node (ref "C26") (pin "2") (pinfunction "2_2") (pintype "passive"))
      (node (ref "C27") (pin "2") (pinfunction "2_2") (pintype "passive"))
      (node (ref "C3") (pin "2") (pinfunction "2_2") (pintype "passive"))
      (node (ref "C5") (pin "2") (pinfunction "2_2") (pintype "passive"))
      (node (ref "C6") (pin "2") (pinfunction "2_2") (pintype "passive"))
      (node (ref "C7") (pin "2") (pinfunction "2_2") (pintype "passive"))
      (node (ref "C8") (pin "2") (pinfunction "2_2") (pintype "passive"))
      (node (ref "C9") (pin "2") (pinfunction "2_2") (pintype "passive"))
      (node (ref "D5") (pin "A") (pinfunction "A_A") (pintype "passive"))
      (node (ref "DC1") (pin "5") (pinfunction "-VOUT_5") (pintype "passive"))
      (node (ref "ESP1") (pin "1") (pinfunction "GND_1") (pintype "power_in"))
      (node (ref "ESP1") (pin "15") (pinfunction "GND_15") (pintype "power_in"))
      (node (ref "ESP1") (pin "38") (pinfunction "GND_38") (pintype "power_in"))
      (node (ref "ESP1") (pin "EP1") (pinfunction "EP_EP1") (pintype "passive"))
      (node (ref "ESP1") (pin "EP2") (pinfunction "EP_EP2") (pintype "passive"))
      (node (ref "ESP1") (pin "EP3") (pinfunction "EP_EP3") (pintype "passive"))
      (node (ref "ESP1") (pin "EP4") (pinfunction "EP_EP4") (pintype "passive"))
      (node (ref "ESP1") (pin "EP5") (pinfunction "EP_EP5") (pintype "passive"))
      (node (ref "ESP1") (pin "EP6") (pinfunction "EP_EP6") (pintype "passive"))
      (node (ref "ESP1") (pin "EP7") (pinfunction "EP_EP7") (pintype "passive"))
      (node (ref "ESP1") (pin "EP8") (pinfunction "EP_EP8") (pintype "passive"))
      (node (ref "ESP1") (pin "EP9") (pinfunction "EP_EP9") (pintype "passive"))
      (node (ref "IC1") (pin "24") (pinfunction "TXD2_24") (pintype "input"))
      (node (ref "IC1") (pin "25") (pinfunction "TXD3_25") (pintype "input"))
      (node (ref "IC1") (pin "EP") (pinfunction "GND_EP") (pintype "power_in"))
      (node (ref "IC4") (pin "2") (pinfunction "GND_2") (pintype "power_in"))
      (node (ref "IC6") (pin "3") (pinfunction "GND_3") (pintype "power_in"))
      (node (ref "OK2") (pin "2") (pinfunction "C_2") (pintype "passive"))
      (node (ref "PGD") (pin "C") (pinfunction "C_C") (pintype "passive"))
      (node (ref "POE-ETH") (pin "12") (pinfunction "YK_12") (pintype "passive"))
      (node (ref "Q3") (pin "2") (pinfunction "E_2") (pintype "passive"))
      (node (ref "R11") (pin "2") (pinfunction "2_2") (pintype "passive"))
      (node (ref "R20") (pin "1") (pinfunction "1_1") (pintype "passive"))
      (node (ref "R35") (pin "2") (pinfunction "2_2") (pintype "passive"))
      (node (ref "R42") (pin "2") (pinfunction "2_2") (pintype "passive"))
      (node (ref "R44") (pin "2") (pinfunction "2_2") (pintype "passive"))
      (node (ref "R47") (pin "2") (pinfunction "2_2") (pintype "passive"))
      (node (ref "R5") (pin "2") (pinfunction "2_2") (pintype "passive"))
      (node (ref "R52") (pin "1") (pinfunction "1_1") (pintype "passive"))
      (node (ref "R8") (pin "1") (pinfunction "1_1") (pintype "passive"))
      (node (ref "RN1") (pin "5") (pinfunction "5_5") (pintype "passive"))
      (node (ref "RN2") (pin "5") (pinfunction "5_5") (pintype "passive"))
      (node (ref "RN2") (pin "6") (pinfunction "6_6") (pintype "passive"))
      (node (ref "RST") (pin "3") (pinfunction "3_3") (pintype "passive"))
      (node (ref "RST") (pin "4") (pinfunction "4_4") (pintype "passive"))
      (node (ref "U1") (pin "2") (pinfunction "GND_2") (pintype "power_in"))
      (node (ref "U2") (pin "2") (pinfunction "GND_2") (pintype "power_in"))
      (node (ref "UEXT") (pin "2") (pinfunction "2_2") (pintype "passive"))
      (node (ref "USB") (pin "GND") (pinfunction "GND_GND") (pintype "bidirectional"))
      (node (ref "USB") (pin "MT1") (pinfunction "GND_MT1") (pintype "bidirectional"))
      (node (ref "USB") (pin "MT2") (pinfunction "GND_MT2") (pintype "bidirectional"))
      (node (ref "USB") (pin "MT3") (pinfunction "GND_MT3") (pintype "bidirectional"))
      (node (ref "USB") (pin "MT4") (pinfunction "GND_MT4") (pintype "bidirectional"))
      (node (ref "USB") (pin "MT5") (pinfunction "GND_MT5") (pintype "bidirectional"))
      (node (ref "USB") (pin "MT6") (pinfunction "GND_MT6") (pintype "bidirectional"))
      (node (ref "USD") (pin "6") (pinfunction "GND_6") (pintype "power_in"))
      (node (ref "USD") (pin "S1") (pinfunction "SHIELD_S1") (pintype "passive"))
      (node (ref "USD") (pin "S2") (pinfunction "SHIELD_S2") (pintype "passive"))
      (node (ref "USD") (pin "S3") (pinfunction "SHIELD_S3") (pintype "passive"))
      (node (ref "USD") (pin "S4") (pinfunction "SHIELD_S4") (pintype "passive"))
    )
    (net (code "38") (name "Net-(BSB-Pad1)") (class "Default")
      (node (ref "BSB") (pin "1") (pinfunction "1_1") (pintype "passive"))
      (node (ref "R10") (pin "1") (pinfunction "1_1") (pintype "passive"))
    )
    (net (code "39") (name "Net-(BSBB-1)") (class "Default")
      (node (ref "BSB") (pin "2") (pinfunction "1_2") (pintype "passive"))
      (node (ref "R9") (pin "1") (pinfunction "1_1") (pintype "passive"))
    )
    (net (code "40") (name "Net-(C2-Pad1)") (class "Default")
      (node (ref "C2") (pin "1") (pinfunction "1_1") (pintype "passive"))
      (node (ref "POE-ETH") (pin "SH1") (pinfunction "SLD_SH1") (pintype "passive"))
      (node (ref "POE-ETH") (pin "SH2") (pinfunction "SLD_SH2") (pintype "passive"))
    )
    (net (code "41") (name "Net-(C17-Pad1)") (class "Default")
      (node (ref "C17") (pin "1") (pinfunction "1_1") (pintype "passive"))
      (node (ref "R39") (pin "2") (pinfunction "2_2") (pintype "passive"))
    )
    (net (code "42") (name "Net-(D2-PadC)") (class "Default")
      (node (ref "D2") (pin "C") (pinfunction "C_C") (pintype "passive"))
      (node (ref "D3") (pin "1") (pinfunction "1_1") (pintype "passive"))
      (node (ref "R9") (pin "2") (pinfunction "2_2") (pintype "passive"))
    )
    (net (code "43") (name "Net-(IC1-NRST)") (class "Default")
      (node (ref "C12") (pin "1") (pinfunction "1_1") (pintype "passive"))
      (node (ref "IC1") (pin "19") (pinfunction "NRST_19") (pintype "input"))
      (node (ref "R19") (pin "1") (pinfunction "1_1") (pintype "passive"))
    )
    (net (code "44") (name "Net-(IC1-RBIAS)") (class "Default")
      (node (ref "IC1") (pin "32") (pinfunction "RBIAS_32") (pintype "passive"))
      (node (ref "R20") (pin "2") (pinfunction "2_2") (pintype "passive"))
    )
    (net (code "45") (name "Net-(IC1-RXN)") (class "Default")
      (node (ref "IC1") (pin "30") (pinfunction "RXN_30") (pintype "bidirectional"))
      (node (ref "POE-ETH") (pin "2") (pinfunction "RD-_2") (pintype "passive"))
      (node (ref "R17") (pin "1") (pinfunction "1_1") (pintype "passive"))
      (node (ref "U1") (pin "3") (pinfunction "IO2_3") (pintype "passive"))
    )
    (net (code "46") (name "Net-(IC1-RXP)") (class "Default")
      (node (ref "IC1") (pin "31") (pinfunction "RXP_31") (pintype "bidirectional"))
      (node (ref "POE-ETH") (pin "1") (pinfunction "RD+_1") (pintype "passive"))
      (node (ref "R18") (pin "2") (pinfunction "2_2") (pintype "passive"))
      (node (ref "U1") (pin "4") (pinfunction "IO3_4") (pintype "passive"))
    )
    (net (code "47") (name "Net-(IC1-TXN)") (class "Default")
      (node (ref "IC1") (pin "28") (pinfunction "TXN_28") (pintype "bidirectional"))
      (node (ref "POE-ETH") (pin "6") (pinfunction "TD-_6") (pintype "passive"))
      (node (ref "R15") (pin "1") (pinfunction "1_1") (pintype "passive"))
      (node (ref "U1") (pin "5") (pinfunction "IO4_5") (pintype "passive"))
    )
    (net (code "48") (name "Net-(IC1-TXP)") (class "Default")
      (node (ref "IC1") (pin "29") (pinfunction "TXP_29") (pintype "bidirectional"))
      (node (ref "POE-ETH") (pin "5") (pinfunction "TD+_5") (pintype "passive"))
      (node (ref "R16") (pin "2") (pinfunction "2_2") (pintype "passive"))
      (node (ref "U1") (pin "1") (pinfunction "IO1_1") (pintype "passive"))
    )
    (net (code "49") (name "Net-(IC1-VDDCR)") (class "Default")
      (node (ref "C10") (pin "1") (pinfunction "1_1") (pintype "passive"))
      (node (ref "C7") (pin "1") (pinfunction "1_1") (pintype "passive"))
      (node (ref "IC1") (pin "6") (pinfunction "VDDCR_6") (pintype "power_in"))
    )
    (net (code "50") (name "Net-(IC2-CLASS)") (class "Default")
      (node (ref "IC2") (pin "2") (pinfunction "CLASS_2") (pintype "input"))
      (node (ref "R27") (pin "1") (pinfunction "1_1") (pintype "passive"))
    )
    (net (code "51") (name "Net-(IC2-DET)") (class "Default")
      (node (ref "IC2") (pin "3") (pinfunction "DET_3") (pintype "input"))
      (node (ref "R25") (pin "2") (pinfunction "2_2") (pintype "passive"))
    )
    (net (code "52") (name "Net-(IC2-ILIM)") (class "Default")
      (node (ref "IC2") (pin "1") (pinfunction "ILIM_1") (pintype "input"))
      (node (ref "R26") (pin "1") (pinfunction "1_1") (pintype "passive"))
    )
    (net (code "53") (name "Net-(IC2-UVLO)") (class "Default")
      (node (ref "IC2") (pin "7") (pinfunction "UVLO_7") (pintype "input"))
      (node (ref "R23") (pin "1") (pinfunction "1_1") (pintype "passive"))
      (node (ref "R24") (pin "2") (pinfunction "2_2") (pintype "passive"))
    )
    (net (code "54") (name "Net-(IC3-BS)") (class "Default")
      (node (ref "IC3") (pin "8") (pinfunction "BS_8") (pintype "power_in"))
      (node (ref "R39") (pin "1") (pinfunction "1_1") (pintype "passive"))
    )
    (net (code "55") (name "Net-(IC3-FB)") (class "Default")
      (node (ref "C19") (pin "2") (pinfunction "2_2") (pintype "passive"))
      (node (ref "IC3") (pin "5") (pinfunction "FB_5") (pintype "input"))
      (node (ref "R36") (pin "1") (pinfunction "1_1") (pintype "passive"))
      (node (ref "R37") (pin "1") (pinfunction "1_1") (pintype "passive"))
    )
    (net (code "56") (name "Net-(IC3-ILIM-Pad2)") (class "Default")
      (node (ref "IC3") (pin "2") (pinfunction "ILIM_2") (pintype "power_in"))
      (node (ref "IC3") (pin "EP") (pinfunction "ILIM_EP") (pintype "power_in"))
      (node (ref "R21") (pin "2") (pinfunction "2_2") (pintype "passive"))
    )
    (net (code "57") (name "Net-(IC3-SW)") (class "Default")
      (node (ref "C17") (pin "2") (pinfunction "2_2") (pintype "passive"))
      (node (ref "D1") (pin "C") (pinfunction "C_C") (pintype "passive"))
      (node (ref "IC3") (pin "1") (pinfunction "SW_1") (pintype "output"))
      (node (ref "L3") (pin "1") (pinfunction "1_1") (pintype "passive"))
    )
    (net (code "58") (name "Net-(IC4-FB)") (class "Default")
      (node (ref "IC4") (pin "5") (pinfunction "FB_5") (pintype "input"))
      (node (ref "R40") (pin "1") (pinfunction "1_1") (pintype "passive"))
      (node (ref "R41") (pin "2") (pinfunction "2_2") (pintype "passive"))
    )
    (net (code "59") (name "Net-(IC4-LX)") (class "Default")
      (node (ref "IC4") (pin "3") (pinfunction "LX_3") (pintype "output"))
      (node (ref "L4") (pin "1") (pinfunction "1_1") (pintype "passive"))
    )
    (net (code "60") (name "Net-(IC6-TNOW{slash}~{DTR})") (class "Default")
      (node (ref "IC6") (pin "6") (pinfunction "TNOW/~{DTR}_6") (pintype "bidirectional"))
      (node (ref "Q5") (pin "2") (pinfunction "E_2") (pintype "passive"))
      (node (ref "R46") (pin "2") (pinfunction "2_2") (pintype "passive"))
      (node (ref "R50") (pin "1") (pinfunction "1_1") (pintype "passive"))
    )
    (net (code "61") (name "Net-(IC6-TXD)") (class "Default")
      (node (ref "IC6") (pin "8") (pinfunction "TXD_8") (pintype "output"))
      (node (ref "R49") (pin "1") (pinfunction "1_1") (pintype "passive"))
    )
    (net (code "62") (name "Net-(IC6-~{CTS})") (class "Default")
      (node (ref "IC6") (pin "5") (pinfunction "~{CTS}_5") (pintype "input"))
      (node (ref "R50") (pin "2") (pinfunction "2_2") (pintype "passive"))
    )
    (net (code "63") (name "Net-(IC6-~{RTS})") (class "Default")
      (node (ref "IC6") (pin "4") (pinfunction "~{RTS}_4") (pintype "output"))
      (node (ref "Q6") (pin "2") (pinfunction "E_2") (pintype "passive"))
      (node (ref "R45") (pin "2") (pinfunction "2_2") (pintype "passive"))
    )
    (net (code "64") (name "Net-(OK1-A)") (class "Default")
      (node (ref "OK1") (pin "1") (pinfunction "A_1") (pintype "passive"))
      (node (ref "R2") (pin "2") (pinfunction "2_2") (pintype "passive"))
    )
    (net (code "65") (name "Net-(OK1-BAS)") (class "Default")
      (node (ref "OK1") (pin "6") (pinfunction "BAS_6") (pintype "passive"))
      (node (ref "R4") (pin "2") (pinfunction "2_2") (pintype "passive"))
    )
    (net (code "66") (name "Net-(OK1-C)") (class "Default")
      (node (ref "ACT") (pin "A") (pinfunction "A_A") (pintype "passive"))
      (node (ref "OK1") (pin "2") (pinfunction "C_2") (pintype "passive"))
    )
    (net (code "67") (name "Net-(OK2-A)") (class "Default")
      (node (ref "OK2") (pin "1") (pinfunction "A_1") (pintype "passive"))
      (node (ref "R3") (pin "2") (pinfunction "2_2") (pintype "passive"))
    )
    (net (code "68") (name "Net-(OK2-BAS)") (class "Default")
      (node (ref "OK2") (pin "6") (pinfunction "BAS_6") (pintype "passive"))
      (node (ref "R1") (pin "2") (pinfunction "2_2") (pintype "passive"))
    )
    (net (code "69") (name "Net-(OK2-EMI)") (class "Default")
      (node (ref "OK2") (pin "4") (pinfunction "EMI_4") (pintype "passive"))
      (node (ref "Q1") (pin "1") (pinfunction "B_1") (pintype "passive"))
      (node (ref "R1") (pin "1") (pinfunction "1_1") (pintype "passive"))
      (node (ref "R7") (pin "2") (pinfunction "2_2") (pintype "passive"))
    )
    (net (code "70") (name "Net-(OPT-Pad2)") (class "Default")
      (node (ref "OPT") (pin "2") (pinfunction "2_2") (pintype "passive"))
      (node (ref "R35") (pin "1") (pinfunction "1_1") (pintype "passive"))
    )
    (net (code "71") (name "Net-(PGD-PadA)") (class "Default")
      (node (ref "PGD") (pin "A") (pinfunction "A_A") (pintype "passive"))
      (node (ref "R48") (pin "1") (pinfunction "1_1") (pintype "passive"))
    )
    (net (code "72") (name "Net-(POE-ETH-GK)") (class "Default")
      (node (ref "POE-ETH") (pin "14") (pinfunction "GK_14") (pintype "passive"))
      (node (ref "R30") (pin "1") (pinfunction "1_1") (pintype "passive"))
    )
    (net (code "73") (name "Net-(POE-ETH-YA)") (class "Default")
      (node (ref "POE-ETH") (pin "11") (pinfunction "YA_11") (pintype "passive"))
      (node (ref "R29") (pin "1") (pinfunction "1_1") (pintype "passive"))
    )
    (net (code "74") (name "Net-(Q2-PadB)") (class "Default")
      (node (ref "Q2") (pin "B") (pinfunction "B_B") (pintype "passive"))
      (node (ref "R6") (pin "1") (pinfunction "1_1") (pintype "passive"))
    )
    (net (code "75") (name "Net-(Q2-PadC)") (class "Default")
      (node (ref "Q2") (pin "C") (pinfunction "C_C") (pintype "passive"))
      (node (ref "R3") (pin "1") (pinfunction "1_1") (pintype "passive"))
    )
    (net (code "76") (name "Net-(Q3-B)") (class "Default")
      (node (ref "Q3") (pin "1") (pinfunction "B_1") (pintype "passive"))
      (node (ref "R11") (pin "1") (pinfunction "1_1") (pintype "passive"))
      (node (ref "R14") (pin "2") (pinfunction "2_2") (pintype "passive"))
    )
    (net (code "77") (name "Net-(Q3-C)") (class "Default")
      (node (ref "Q3") (pin "3") (pinfunction "C_3") (pintype "passive"))
      (node (ref "R12") (pin "1") (pinfunction "1_1") (pintype "passive"))
    )
    (net (code "78") (name "Net-(Q4-G)") (class "Default")
      (node (ref "C4") (pin "2") (pinfunction "2_2") (pintype "passive"))
      (node (ref "Q4") (pin "1") (pinfunction "G_1") (pintype "passive"))
      (node (ref "R12") (pin "2") (pinfunction "2_2") (pintype "passive"))
      (node (ref "R13") (pin "1") (pinfunction "1_1") (pintype "passive"))
    )
    (net (code "79") (name "Net-(Q5-B)") (class "Default")
      (node (ref "Q5") (pin "1") (pinfunction "B_1") (pintype "passive"))
      (node (ref "R45") (pin "1") (pinfunction "1_1") (pintype "passive"))
    )
    (net (code "80") (name "Net-(Q6-B)") (class "Default")
      (node (ref "Q6") (pin "1") (pinfunction "B_1") (pintype "passive"))
      (node (ref "R46") (pin "1") (pinfunction "1_1") (pintype "passive"))
    )
    (net (code "81") (name "Net-(R36-Pad2)") (class "Default")
      (node (ref "R36") (pin "2") (pinfunction "2_2") (pintype "passive"))
      (node (ref "R38") (pin "2") (pinfunction "2_2") (pintype "passive"))
    )
    (net (code "82") (name "Net-(R41-Pad1)") (class "Default")
      (node (ref "R41") (pin "1") (pinfunction "1_1") (pintype "passive"))
      (node (ref "R42") (pin "1") (pinfunction "1_1") (pintype "passive"))
    )
    (net (code "83") (name "Net-(USD-CS{slash}DAT3)") (class "Default")
      (node (ref "RN3") (pin "2") (pinfunction "2_2") (pintype "passive"))
      (node (ref "USD") (pin "2") (pinfunction "CS/DAT3_2") (pintype "bidirectional"))
    )
    (net (code "84") (name "Net-(USD-DAT0)") (class "Default")
      (node (ref "R31") (pin "2") (pinfunction "2_2") (pintype "passive"))
      (node (ref "USD") (pin "7") (pinfunction "DAT0_7") (pintype "bidirectional"))
    )
    (net (code "85") (name "Net-(USD-DAT1)") (class "Default")
      (node (ref "RN3") (pin "3") (pinfunction "3_3") (pintype "passive"))
      (node (ref "USD") (pin "8") (pinfunction "DAT1_8") (pintype "bidirectional"))
    )
    (net (code "86") (name "Net-(USD-DAT2)") (class "Default")
      (node (ref "RN3") (pin "1") (pinfunction "1_1") (pintype "passive"))
      (node (ref "USD") (pin "1") (pinfunction "DAT2_1") (pintype "bidirectional"))
    )
    (net (code "87") (name "Net-(USD-SCLK)") (class "Default")
      (node (ref "R33") (pin "2") (pinfunction "2_2") (pintype "passive"))
      (node (ref "USD") (pin "5") (pinfunction "SCLK_5") (pintype "bidirectional"))
    )
    (net (code "88") (name "PHY-PWR") (class "Default")
      (node (ref "ESP1") (pin "14") (pinfunction "GPIO12_14") (pintype "bidirectional"))
      (node (ref "R14") (pin "1") (pinfunction "1_1") (pintype "passive"))
    )
    (net (code "89") (name "POE-5V0") (class "Default")
      (node (ref "C18") (pin "+") (pinfunction "+_+") (pintype "passive"))
      (node (ref "C19") (pin "1") (pinfunction "1_1") (pintype "passive"))
      (node (ref "C20") (pin "1") (pinfunction "1_1") (pintype "passive"))
      (node (ref "C22") (pin "1") (pinfunction "1_1") (pintype "passive"))
      (node (ref "DC1") (pin "1") (pinfunction "+VIN_1") (pintype "passive"))
      (node (ref "L3") (pin "2") (pinfunction "2_2") (pintype "passive"))
      (node (ref "R38") (pin "1") (pinfunction "1_1") (pintype "passive"))
    )
    (net (code "90") (name "POE-GND") (class "Default")
      (node (ref "C14") (pin "-") (pinfunction "-_-") (pintype "passive"))
      (node (ref "C18") (pin "-") (pinfunction "-_-") (pintype "passive"))
      (node (ref "C21") (pin "1") (pinfunction "1_1") (pintype "passive"))
      (node (ref "C22") (pin "2") (pinfunction "2_2") (pintype "passive"))
      (node (ref "D1") (pin "A") (pinfunction "A_A") (pintype "passive"))
      (node (ref "DC1") (pin "2") (pinfunction "-VIN_2") (pintype "passive"))
      (node (ref "IC2") (pin "5") (pinfunction "RTN_5") (pintype "power_in"))
      (node (ref "IC3") (pin "4") (pinfunction "GND_4") (pintype "power_in"))
      (node (ref "R22") (pin "2") (pinfunction "2_2") (pintype "passive"))
      (node (ref "R37") (pin "2") (pinfunction "2_2") (pintype "passive"))
    )
    (net (code "91") (name "POE-PG") (class "Default")
      (node (ref "IC2") (pin "6") (pinfunction "PG_6") (pintype "output"))
      (node (ref "IC3") (pin "6") (pinfunction "EN_6") (pintype "input"))
    )
    (net (code "92") (name "POE-V+") (class "Default")
      (node (ref "C13") (pin "1") (pinfunction "1_1") (pintype "passive"))
      (node (ref "C14") (pin "+") (pinfunction "+_+") (pintype "passive"))
      (node (ref "D4") (pin "C") (pinfunction "C_C") (pintype "passive"))
      (node (ref "IC2") (pin "8") (pinfunction "VDD_8") (pintype "power_in"))
      (node (ref "IC3") (pin "3") (pinfunction "VIN_3") (pintype "power_in"))
      (node (ref "POE-ETH") (pin "9") (pinfunction "V+_9") (pintype "output"))
      (node (ref "R21") (pin "1") (pinfunction "1_1") (pintype "passive"))
      (node (ref "R22") (pin "1") (pinfunction "1_1") (pintype "passive"))
      (node (ref "R24") (pin "1") (pinfunction "1_1") (pintype "passive"))
      (node (ref "R25") (pin "1") (pinfunction "1_1") (pintype "passive"))
    )
    (net (code "93") (name "POE-V-") (class "Default")
      (node (ref "C13") (pin "2") (pinfunction "2_2") (pintype "passive"))
      (node (ref "D4") (pin "A") (pinfunction "A_A") (pintype "passive"))
      (node (ref "IC2") (pin "4") (pinfunction "VSS_4") (pintype "power_in"))
      (node (ref "IC2") (pin "EP") (pinfunction "VSS_EP") (pintype "power_in"))
      (node (ref "POE-ETH") (pin "10") (pinfunction "V-_10") (pintype "output"))
      (node (ref "R23") (pin "2") (pinfunction "2_2") (pintype "passive"))
      (node (ref "R26") (pin "2") (pinfunction "2_2") (pintype "passive"))
      (node (ref "R27") (pin "2") (pinfunction "2_2") (pintype "passive"))
    )
    (net (code "94") (name "PWR-SNS") (class "Default")
      (node (ref "C27") (pin "1") (pinfunction "1_1") (pintype "passive"))
      (node (ref "ESP1") (pin "5") (pinfunction "SENSOR_VN_5") (pintype "bidirectional"))
      (node (ref "R43") (pin "2") (pinfunction "2_2") (pintype "passive"))
      (node (ref "R44") (pin "1") (pinfunction "1_1") (pintype "passive"))
    )
    (net (code "95") (name "SD-VCC") (class "Default")
      (node (ref "C15") (pin "1") (pinfunction "1_1") (pintype "passive"))
      (node (ref "C16") (pin "1") (pinfunction "1_1") (pintype "passive"))
      (node (ref "L2") (pin "2") (pinfunction "2_2") (pintype "passive"))
      (node (ref "USD") (pin "4") (pinfunction "VCC_4") (pintype "power_in"))
    )
    (net (code "96") (name "UEXT-RX") (class "Default")
      (node (ref "ESP1") (pin "7") (pinfunction "GPIO35_7") (pintype "bidirectional"))
      (node (ref "RN4") (pin "4") (pinfunction "4_4") (pintype "passive"))
      (node (ref "UEXT") (pin "4") (pinfunction "4_4") (pintype "passive"))
    )
    (net (code "97") (name "UEXT-TX") (class "Default")
      (node (ref "ESP1") (pin "9") (pinfunction "GPIO33_9") (pintype "bidirectional"))
      (node (ref "UEXT") (pin "3") (pinfunction "3_3") (pintype "passive"))
    )
    (net (code "98") (name "USB-D_N") (class "Default")
      (node (ref "IC6") (pin "2") (pinfunction "D-_2") (pintype "bidirectional"))
      (node (ref "U2") (pin "1") (pinfunction "IO1_1") (pintype "passive"))
      (node (ref "USB") (pin "D-") (pinfunction "D-_D-") (pintype "bidirectional"))
    )
    (net (code "99") (name "USB-D_P") (class "Default")
      (node (ref "IC6") (pin "1") (pinfunction "D+_1") (pintype "bidirectional"))
      (node (ref "U2") (pin "5") (pinfunction "IO4_5") (pintype "passive"))
      (node (ref "USB") (pin "D+") (pinfunction "D+_D+") (pintype "bidirectional"))
    )
    (net (code "100") (name "USB-VBUS") (class "Default")
      (node (ref "Q7") (pin "3") (pinfunction "D_3") (pintype "passive"))
      (node (ref "USB") (pin "VBUS") (pinfunction "VCC_VBUS") (pintype "bidirectional"))
    )
    (net (code "101") (name "unconnected-(IC1-CRS-Pad14)") (class "Default")
      (node (ref "IC1") (pin "14") (pinfunction "CRS_14") (pintype "bidirectional"))
    )
    (net (code "102") (name "unconnected-(IC1-RXDV-Pad26)") (class "Default")
      (node (ref "IC1") (pin "26") (pinfunction "RXDV_26") (pintype "bidirectional"))
    )
    (net (code "103") (name "unconnected-(IC1-TXCLK-Pad20)") (class "Default")
      (node (ref "IC1") (pin "20") (pinfunction "TXCLK_20") (pintype "bidirectional"))
    )
    (net (code "104") (name "unconnected-(IC1-TXER{slash}TXD4-Pad18)") (class "Default")
      (node (ref "IC1") (pin "18") (pinfunction "TXER/TXD4_18") (pintype "bidirectional"))
    )
    (net (code "105") (name "unconnected-(IC1-XTAL2-Pad4)") (class "Default")
      (node (ref "IC1") (pin "4") (pinfunction "XTAL2_4") (pintype "output"))
    )
    (net (code "106") (name "unconnected-(IC3-POK-Pad7)") (class "Default")
      (node (ref "IC3") (pin "7") (pinfunction "POK_7") (pintype "output"))
    )
    (net (code "107") (name "unconnected-(RST-Pad2)") (class "Default")
      (node (ref "RST") (pin "2") (pinfunction "2_2") (pintype "passive"))
    )
    (net (code "108") (name "unconnected-(U2-IO3-Pad4)") (class "Default")
      (node (ref "U2") (pin "4") (pinfunction "IO3_4") (pintype "passive"))
    )
    (net (code "109") (name "unconnected-(USB-PadID)") (class "Default")
      (node (ref "USB") (pin "ID") (pinfunction "ID_ID") (pintype "bidirectional"))
    )
    (net (code "110") (name "unconnected-(USD-CDET-Pad9)") (class "Default")
      (node (ref "USD") (pin "9") (pinfunction "CDET_9") (pintype "passive"))
    )
  )
)
